# 1-POWER.net
KiCad netlist of a schematic drawn in Altium Designer
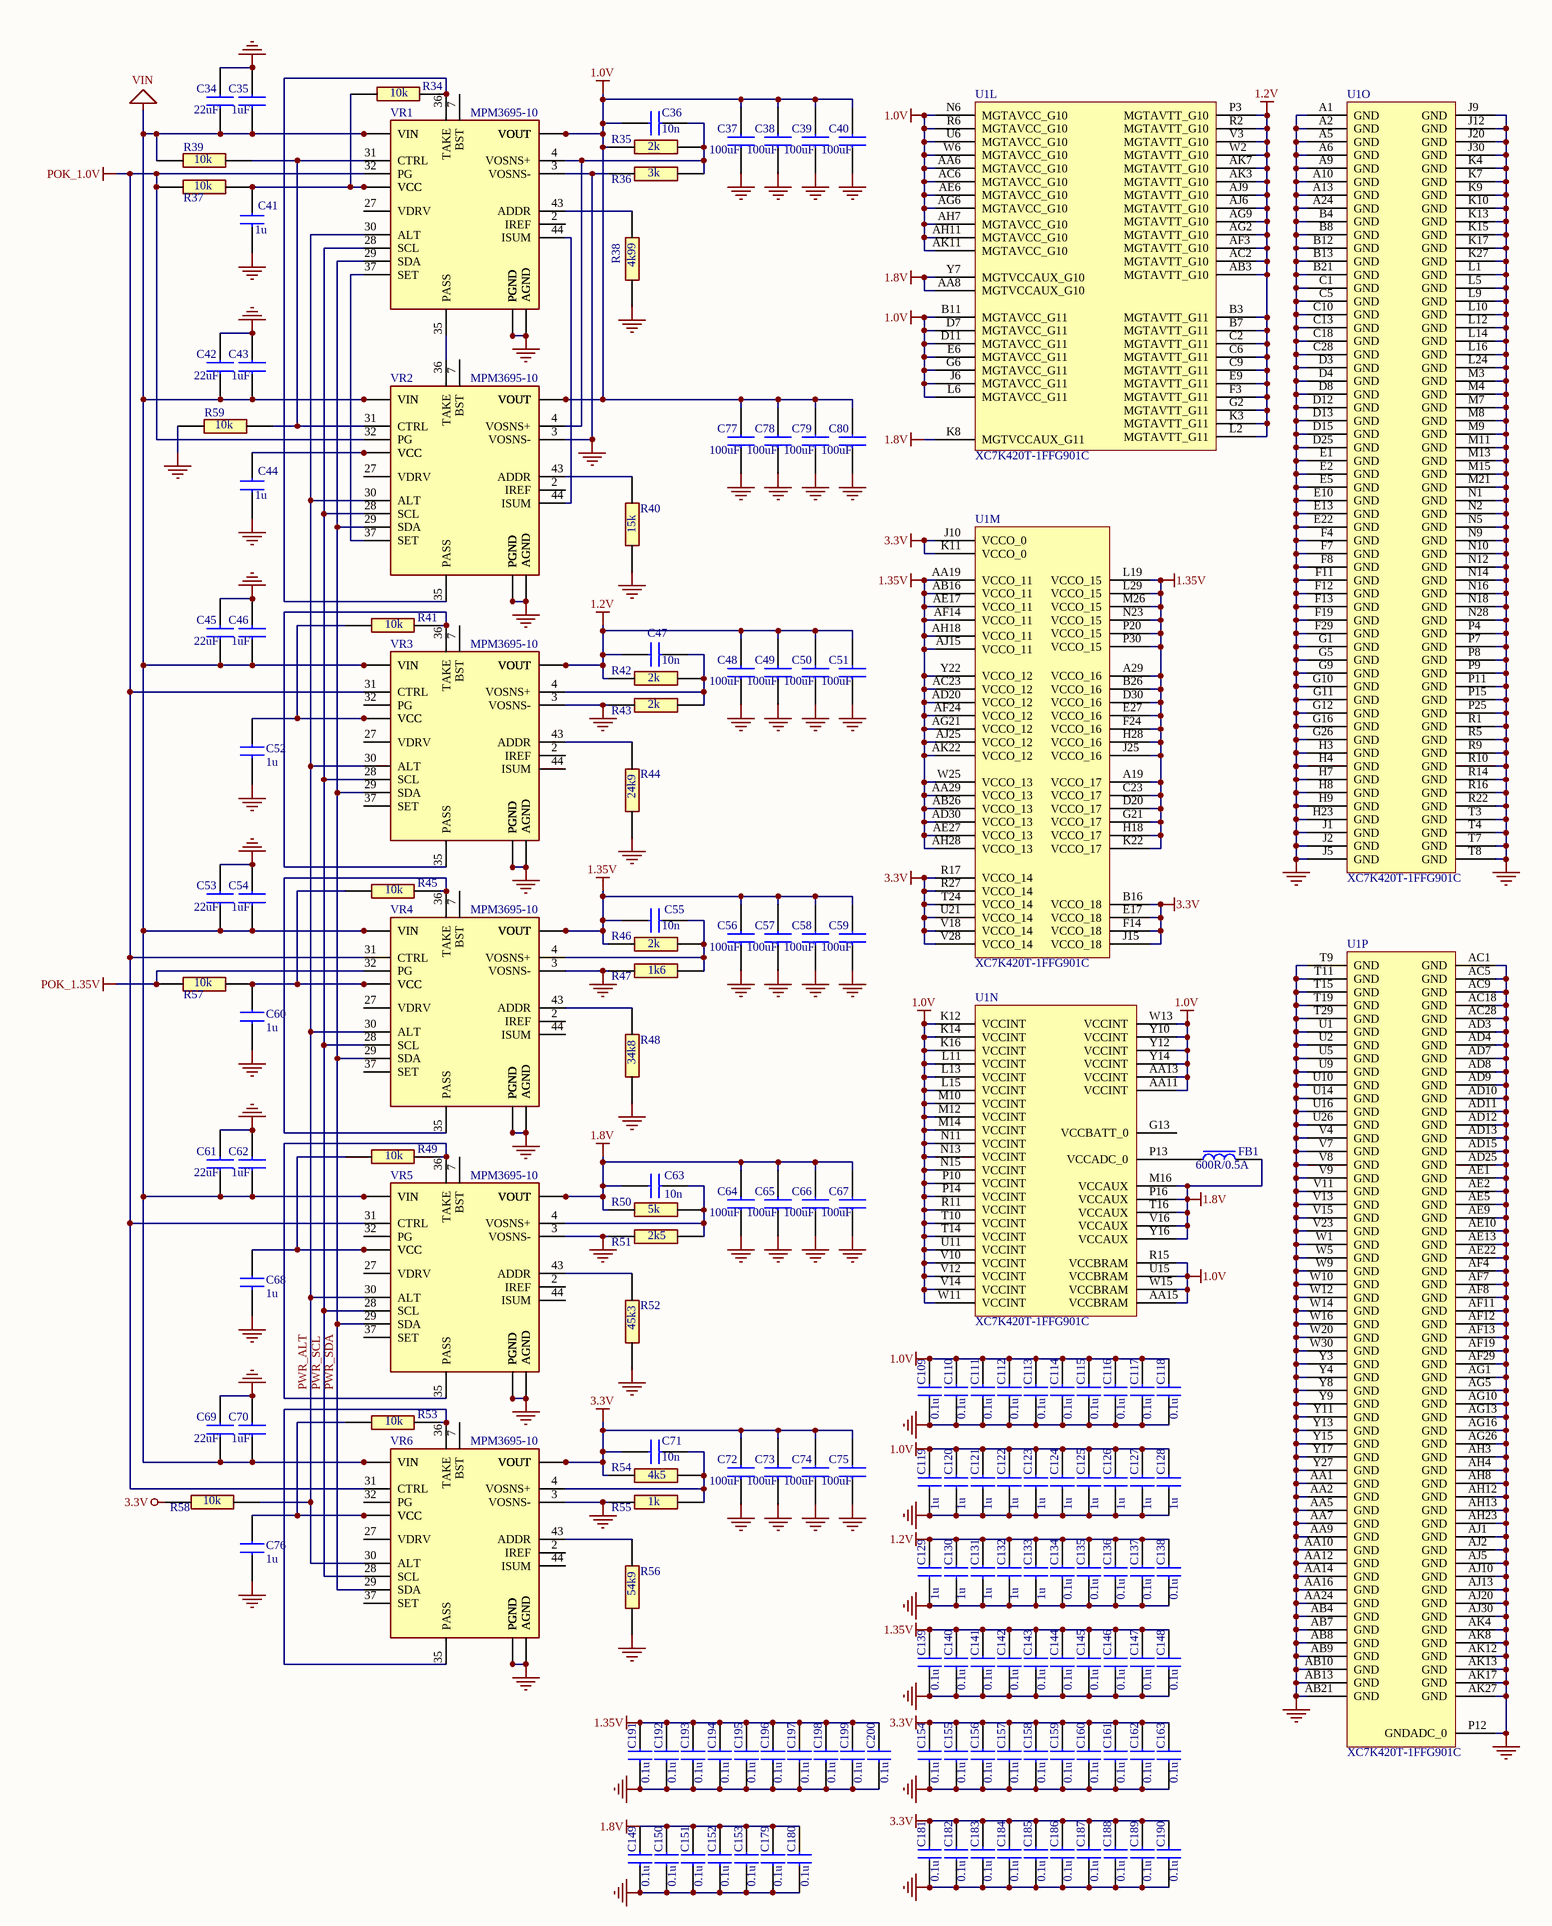
[diagram p0: 1-POWER.SchDoc]

(export (version "E")
  (design (tool "Eeschema 10.0.6"))
  (components
    (comp (ref "C34")
      (value "22uF")
      (footprint "CAPC3225X280N")
      (description "Capacitor")
      (fields
        (field (name "MANUFACTURER_PART_NUMBER") "JMK325ABJ107MM-P")
        (field (name "MOUSER PART NUMBER") "963-JMK325ABJ107MM-P")
      )
      (libsource (lib "m-BLANC") (part "CAP 3225"))
    )
    (comp (ref "C35")
      (value "1uF")
      (footprint "CAPC3225X280N")
      (description "Capacitor")
      (fields
        (field (name "MANUFACTURER_PART_NUMBER") "JMK325ABJ107MM-P")
        (field (name "MOUSER PART NUMBER") "963-JMK325ABJ107MM-P")
      )
      (libsource (lib "m-BLANC") (part "CAP 3225"))
    )
    (comp (ref "C36")
      (value "10n")
      (footprint "SMD0402")
      (description "Capacitor")
      (libsource (lib "m-BLANC") (part "CAP 0402"))
    )
    (comp (ref "C37")
      (value "100uF")
      (footprint "CAPC3225X280N")
      (description "Capacitor")
      (fields
        (field (name "MANUFACTURER_PART_NUMBER") "JMK325ABJ107MM-P")
        (field (name "MOUSER PART NUMBER") "963-JMK325ABJ107MM-P")
      )
      (libsource (lib "m-BLANC") (part "CAP 3225"))
    )
    (comp (ref "C38")
      (value "100uF")
      (footprint "CAPC3225X280N")
      (description "Capacitor")
      (fields
        (field (name "MANUFACTURER_PART_NUMBER") "JMK325ABJ107MM-P")
        (field (name "MOUSER PART NUMBER") "963-JMK325ABJ107MM-P")
      )
      (libsource (lib "m-BLANC") (part "CAP 3225"))
    )
    (comp (ref "C39")
      (value "100uF")
      (footprint "CAPC3225X280N")
      (description "Capacitor")
      (fields
        (field (name "MANUFACTURER_PART_NUMBER") "JMK325ABJ107MM-P")
        (field (name "MOUSER PART NUMBER") "963-JMK325ABJ107MM-P")
      )
      (libsource (lib "m-BLANC") (part "CAP 3225"))
    )
    (comp (ref "C40")
      (value "100uF")
      (footprint "CAPC3225X280N")
      (description "Capacitor")
      (fields
        (field (name "MANUFACTURER_PART_NUMBER") "JMK325ABJ107MM-P")
        (field (name "MOUSER PART NUMBER") "963-JMK325ABJ107MM-P")
      )
      (libsource (lib "m-BLANC") (part "CAP 3225"))
    )
    (comp (ref "C41")
      (value "1u")
      (footprint "SMD0402")
      (description "Capacitor")
      (libsource (lib "m-BLANC") (part "CAP 0402"))
    )
    (comp (ref "C42")
      (value "22uF")
      (footprint "CAPC3225X280N")
      (description "Capacitor")
      (fields
        (field (name "MANUFACTURER_PART_NUMBER") "JMK325ABJ107MM-P")
        (field (name "MOUSER PART NUMBER") "963-JMK325ABJ107MM-P")
      )
      (libsource (lib "m-BLANC") (part "CAP 3225"))
    )
    (comp (ref "C43")
      (value "1uF")
      (footprint "CAPC3225X280N")
      (description "Capacitor")
      (fields
        (field (name "MANUFACTURER_PART_NUMBER") "JMK325ABJ107MM-P")
        (field (name "MOUSER PART NUMBER") "963-JMK325ABJ107MM-P")
      )
      (libsource (lib "m-BLANC") (part "CAP 3225"))
    )
    (comp (ref "C44")
      (value "1u")
      (footprint "SMD0402")
      (description "Capacitor")
      (libsource (lib "m-BLANC") (part "CAP 0402"))
    )
    (comp (ref "C45")
      (value "22uF")
      (footprint "CAPC3225X280N")
      (description "Capacitor")
      (fields
        (field (name "MANUFACTURER_PART_NUMBER") "JMK325ABJ107MM-P")
        (field (name "MOUSER PART NUMBER") "963-JMK325ABJ107MM-P")
      )
      (libsource (lib "m-BLANC") (part "CAP 3225"))
    )
    (comp (ref "C46")
      (value "1uF")
      (footprint "CAPC3225X280N")
      (description "Capacitor")
      (fields
        (field (name "MANUFACTURER_PART_NUMBER") "JMK325ABJ107MM-P")
        (field (name "MOUSER PART NUMBER") "963-JMK325ABJ107MM-P")
      )
      (libsource (lib "m-BLANC") (part "CAP 3225"))
    )
    (comp (ref "C47")
      (value "10n")
      (footprint "SMD0402")
      (description "Capacitor")
      (libsource (lib "m-BLANC") (part "CAP 0402"))
    )
    (comp (ref "C48")
      (value "100uF")
      (footprint "CAPC3225X280N")
      (description "Capacitor")
      (fields
        (field (name "MANUFACTURER_PART_NUMBER") "JMK325ABJ107MM-P")
        (field (name "MOUSER PART NUMBER") "963-JMK325ABJ107MM-P")
      )
      (libsource (lib "m-BLANC") (part "CAP 3225"))
    )
    (comp (ref "C49")
      (value "100uF")
      (footprint "CAPC3225X280N")
      (description "Capacitor")
      (fields
        (field (name "MANUFACTURER_PART_NUMBER") "JMK325ABJ107MM-P")
        (field (name "MOUSER PART NUMBER") "963-JMK325ABJ107MM-P")
      )
      (libsource (lib "m-BLANC") (part "CAP 3225"))
    )
    (comp (ref "C50")
      (value "100uF")
      (footprint "CAPC3225X280N")
      (description "Capacitor")
      (fields
        (field (name "MANUFACTURER_PART_NUMBER") "JMK325ABJ107MM-P")
        (field (name "MOUSER PART NUMBER") "963-JMK325ABJ107MM-P")
      )
      (libsource (lib "m-BLANC") (part "CAP 3225"))
    )
    (comp (ref "C51")
      (value "100uF")
      (footprint "CAPC3225X280N")
      (description "Capacitor")
      (fields
        (field (name "MANUFACTURER_PART_NUMBER") "JMK325ABJ107MM-P")
        (field (name "MOUSER PART NUMBER") "963-JMK325ABJ107MM-P")
      )
      (libsource (lib "m-BLANC") (part "CAP 3225"))
    )
    (comp (ref "C52")
      (value "1u")
      (footprint "SMD0402")
      (description "Capacitor")
      (libsource (lib "m-BLANC") (part "CAP 0402"))
    )
    (comp (ref "C53")
      (value "22uF")
      (footprint "CAPC3225X280N")
      (description "Capacitor")
      (fields
        (field (name "MANUFACTURER_PART_NUMBER") "JMK325ABJ107MM-P")
        (field (name "MOUSER PART NUMBER") "963-JMK325ABJ107MM-P")
      )
      (libsource (lib "m-BLANC") (part "CAP 3225"))
    )
    (comp (ref "C54")
      (value "1uF")
      (footprint "CAPC3225X280N")
      (description "Capacitor")
      (fields
        (field (name "MANUFACTURER_PART_NUMBER") "JMK325ABJ107MM-P")
        (field (name "MOUSER PART NUMBER") "963-JMK325ABJ107MM-P")
      )
      (libsource (lib "m-BLANC") (part "CAP 3225"))
    )
    (comp (ref "C55")
      (value "10n")
      (footprint "SMD0402")
      (description "Capacitor")
      (libsource (lib "m-BLANC") (part "CAP 0402"))
    )
    (comp (ref "C56")
      (value "100uF")
      (footprint "CAPC3225X280N")
      (description "Capacitor")
      (fields
        (field (name "MANUFACTURER_PART_NUMBER") "JMK325ABJ107MM-P")
        (field (name "MOUSER PART NUMBER") "963-JMK325ABJ107MM-P")
      )
      (libsource (lib "m-BLANC") (part "CAP 3225"))
    )
    (comp (ref "C57")
      (value "100uF")
      (footprint "CAPC3225X280N")
      (description "Capacitor")
      (fields
        (field (name "MANUFACTURER_PART_NUMBER") "JMK325ABJ107MM-P")
        (field (name "MOUSER PART NUMBER") "963-JMK325ABJ107MM-P")
      )
      (libsource (lib "m-BLANC") (part "CAP 3225"))
    )
    (comp (ref "C58")
      (value "100uF")
      (footprint "CAPC3225X280N")
      (description "Capacitor")
      (fields
        (field (name "MANUFACTURER_PART_NUMBER") "JMK325ABJ107MM-P")
        (field (name "MOUSER PART NUMBER") "963-JMK325ABJ107MM-P")
      )
      (libsource (lib "m-BLANC") (part "CAP 3225"))
    )
    (comp (ref "C59")
      (value "100uF")
      (footprint "CAPC3225X280N")
      (description "Capacitor")
      (fields
        (field (name "MANUFACTURER_PART_NUMBER") "JMK325ABJ107MM-P")
        (field (name "MOUSER PART NUMBER") "963-JMK325ABJ107MM-P")
      )
      (libsource (lib "m-BLANC") (part "CAP 3225"))
    )
    (comp (ref "C60")
      (value "1u")
      (footprint "SMD0402")
      (description "Capacitor")
      (libsource (lib "m-BLANC") (part "CAP 0402"))
    )
    (comp (ref "C61")
      (value "22uF")
      (footprint "CAPC3225X280N")
      (description "Capacitor")
      (fields
        (field (name "MANUFACTURER_PART_NUMBER") "JMK325ABJ107MM-P")
        (field (name "MOUSER PART NUMBER") "963-JMK325ABJ107MM-P")
      )
      (libsource (lib "m-BLANC") (part "CAP 3225"))
    )
    (comp (ref "C62")
      (value "1uF")
      (footprint "CAPC3225X280N")
      (description "Capacitor")
      (fields
        (field (name "MANUFACTURER_PART_NUMBER") "JMK325ABJ107MM-P")
        (field (name "MOUSER PART NUMBER") "963-JMK325ABJ107MM-P")
      )
      (libsource (lib "m-BLANC") (part "CAP 3225"))
    )
    (comp (ref "C63")
      (value "10n")
      (footprint "SMD0402")
      (description "Capacitor")
      (libsource (lib "m-BLANC") (part "CAP 0402"))
    )
    (comp (ref "C64")
      (value "100uF")
      (footprint "CAPC3225X280N")
      (description "Capacitor")
      (fields
        (field (name "MANUFACTURER_PART_NUMBER") "JMK325ABJ107MM-P")
        (field (name "MOUSER PART NUMBER") "963-JMK325ABJ107MM-P")
      )
      (libsource (lib "m-BLANC") (part "CAP 3225"))
    )
    (comp (ref "C65")
      (value "100uF")
      (footprint "CAPC3225X280N")
      (description "Capacitor")
      (fields
        (field (name "MANUFACTURER_PART_NUMBER") "JMK325ABJ107MM-P")
        (field (name "MOUSER PART NUMBER") "963-JMK325ABJ107MM-P")
      )
      (libsource (lib "m-BLANC") (part "CAP 3225"))
    )
    (comp (ref "C66")
      (value "100uF")
      (footprint "CAPC3225X280N")
      (description "Capacitor")
      (fields
        (field (name "MANUFACTURER_PART_NUMBER") "JMK325ABJ107MM-P")
        (field (name "MOUSER PART NUMBER") "963-JMK325ABJ107MM-P")
      )
      (libsource (lib "m-BLANC") (part "CAP 3225"))
    )
    (comp (ref "C67")
      (value "100uF")
      (footprint "CAPC3225X280N")
      (description "Capacitor")
      (fields
        (field (name "MANUFACTURER_PART_NUMBER") "JMK325ABJ107MM-P")
        (field (name "MOUSER PART NUMBER") "963-JMK325ABJ107MM-P")
      )
      (libsource (lib "m-BLANC") (part "CAP 3225"))
    )
    (comp (ref "C68")
      (value "1u")
      (footprint "SMD0402")
      (description "Capacitor")
      (libsource (lib "m-BLANC") (part "CAP 0402"))
    )
    (comp (ref "C69")
      (value "22uF")
      (footprint "CAPC3225X280N")
      (description "Capacitor")
      (fields
        (field (name "MANUFACTURER_PART_NUMBER") "JMK325ABJ107MM-P")
        (field (name "MOUSER PART NUMBER") "963-JMK325ABJ107MM-P")
      )
      (libsource (lib "") (part "CAP 3225_1"))
    )
    (comp (ref "C70")
      (value "1uF")
      (footprint "CAPC3225X280N")
      (description "Capacitor")
      (fields
        (field (name "MANUFACTURER_PART_NUMBER") "JMK325ABJ107MM-P")
        (field (name "MOUSER PART NUMBER") "963-JMK325ABJ107MM-P")
      )
      (libsource (lib "") (part "CAP 3225_1"))
    )
    (comp (ref "C71")
      (value "10n")
      (footprint "SMD0402")
      (description "Capacitor")
      (libsource (lib "m-BLANC") (part "CAP 0402"))
    )
    (comp (ref "C72")
      (value "100uF")
      (footprint "CAPC3225X280N")
      (description "Capacitor")
      (fields
        (field (name "MANUFACTURER_PART_NUMBER") "JMK325ABJ107MM-P")
        (field (name "MOUSER PART NUMBER") "963-JMK325ABJ107MM-P")
      )
      (libsource (lib "m-BLANC") (part "CAP 3225"))
    )
    (comp (ref "C73")
      (value "100uF")
      (footprint "CAPC3225X280N")
      (description "Capacitor")
      (fields
        (field (name "MANUFACTURER_PART_NUMBER") "JMK325ABJ107MM-P")
        (field (name "MOUSER PART NUMBER") "963-JMK325ABJ107MM-P")
      )
      (libsource (lib "m-BLANC") (part "CAP 3225"))
    )
    (comp (ref "C74")
      (value "100uF")
      (footprint "CAPC3225X280N")
      (description "Capacitor")
      (fields
        (field (name "MANUFACTURER_PART_NUMBER") "JMK325ABJ107MM-P")
        (field (name "MOUSER PART NUMBER") "963-JMK325ABJ107MM-P")
      )
      (libsource (lib "m-BLANC") (part "CAP 3225"))
    )
    (comp (ref "C75")
      (value "100uF")
      (footprint "CAPC3225X280N")
      (description "Capacitor")
      (fields
        (field (name "MANUFACTURER_PART_NUMBER") "JMK325ABJ107MM-P")
        (field (name "MOUSER PART NUMBER") "963-JMK325ABJ107MM-P")
      )
      (libsource (lib "m-BLANC") (part "CAP 3225"))
    )
    (comp (ref "C76")
      (value "1u")
      (footprint "SMD0402")
      (description "Capacitor")
      (libsource (lib "m-BLANC") (part "CAP 0402"))
    )
    (comp (ref "C77")
      (value "100uF")
      (footprint "CAPC3225X280N")
      (description "Capacitor")
      (fields
        (field (name "MANUFACTURER_PART_NUMBER") "JMK325ABJ107MM-P")
        (field (name "MOUSER PART NUMBER") "963-JMK325ABJ107MM-P")
      )
      (libsource (lib "m-BLANC") (part "CAP 3225"))
    )
    (comp (ref "C78")
      (value "100uF")
      (footprint "CAPC3225X280N")
      (description "Capacitor")
      (fields
        (field (name "MANUFACTURER_PART_NUMBER") "JMK325ABJ107MM-P")
        (field (name "MOUSER PART NUMBER") "963-JMK325ABJ107MM-P")
      )
      (libsource (lib "m-BLANC") (part "CAP 3225"))
    )
    (comp (ref "C79")
      (value "100uF")
      (footprint "CAPC3225X280N")
      (description "Capacitor")
      (fields
        (field (name "MANUFACTURER_PART_NUMBER") "JMK325ABJ107MM-P")
        (field (name "MOUSER PART NUMBER") "963-JMK325ABJ107MM-P")
      )
      (libsource (lib "m-BLANC") (part "CAP 3225"))
    )
    (comp (ref "C80")
      (value "100uF")
      (footprint "CAPC3225X280N")
      (description "Capacitor")
      (fields
        (field (name "MANUFACTURER_PART_NUMBER") "JMK325ABJ107MM-P")
        (field (name "MOUSER PART NUMBER") "963-JMK325ABJ107MM-P")
      )
      (libsource (lib "m-BLANC") (part "CAP 3225"))
    )
    (comp (ref "C109")
      (value "0.1u")
      (footprint "SMD0402")
      (description "Capacitor")
      (libsource (lib "") (part "CAP 0402_1"))
    )
    (comp (ref "C110")
      (value "0.1u")
      (footprint "SMD0402")
      (description "Capacitor")
      (libsource (lib "") (part "CAP 0402_1"))
    )
    (comp (ref "C111")
      (value "0.1u")
      (footprint "SMD0402")
      (description "Capacitor")
      (libsource (lib "") (part "CAP 0402_1"))
    )
    (comp (ref "C112")
      (value "0.1u")
      (footprint "SMD0402")
      (description "Capacitor")
      (libsource (lib "") (part "CAP 0402_1"))
    )
    (comp (ref "C113")
      (value "0.1u")
      (footprint "SMD0402")
      (description "Capacitor")
      (libsource (lib "") (part "CAP 0402_1"))
    )
    (comp (ref "C114")
      (value "0.1u")
      (footprint "SMD0402")
      (description "Capacitor")
      (libsource (lib "") (part "CAP 0402_1"))
    )
    (comp (ref "C115")
      (value "0.1u")
      (footprint "SMD0402")
      (description "Capacitor")
      (libsource (lib "") (part "CAP 0402_1"))
    )
    (comp (ref "C116")
      (value "0.1u")
      (footprint "SMD0402")
      (description "Capacitor")
      (libsource (lib "") (part "CAP 0402_1"))
    )
    (comp (ref "C117")
      (value "0.1u")
      (footprint "SMD0402")
      (description "Capacitor")
      (libsource (lib "") (part "CAP 0402_1"))
    )
    (comp (ref "C118")
      (value "0.1u")
      (footprint "SMD0402")
      (description "Capacitor")
      (libsource (lib "") (part "CAP 0402_1"))
    )
    (comp (ref "C119")
      (value "1u")
      (footprint "SMD0402")
      (description "Capacitor")
      (libsource (lib "m-BLANC") (part "CAP 0402"))
    )
    (comp (ref "C120")
      (value "1u")
      (footprint "SMD0402")
      (description "Capacitor")
      (libsource (lib "m-BLANC") (part "CAP 0402"))
    )
    (comp (ref "C121")
      (value "1u")
      (footprint "SMD0402")
      (description "Capacitor")
      (libsource (lib "m-BLANC") (part "CAP 0402"))
    )
    (comp (ref "C122")
      (value "1u")
      (footprint "SMD0402")
      (description "Capacitor")
      (libsource (lib "m-BLANC") (part "CAP 0402"))
    )
    (comp (ref "C123")
      (value "1u")
      (footprint "SMD0402")
      (description "Capacitor")
      (libsource (lib "m-BLANC") (part "CAP 0402"))
    )
    (comp (ref "C124")
      (value "1u")
      (footprint "SMD0402")
      (description "Capacitor")
      (libsource (lib "m-BLANC") (part "CAP 0402"))
    )
    (comp (ref "C125")
      (value "1u")
      (footprint "SMD0402")
      (description "Capacitor")
      (libsource (lib "m-BLANC") (part "CAP 0402"))
    )
    (comp (ref "C126")
      (value "1u")
      (footprint "SMD0402")
      (description "Capacitor")
      (libsource (lib "m-BLANC") (part "CAP 0402"))
    )
    (comp (ref "C127")
      (value "1u")
      (footprint "SMD0402")
      (description "Capacitor")
      (libsource (lib "m-BLANC") (part "CAP 0402"))
    )
    (comp (ref "C128")
      (value "1u")
      (footprint "SMD0402")
      (description "Capacitor")
      (libsource (lib "m-BLANC") (part "CAP 0402"))
    )
    (comp (ref "C129")
      (value "1u")
      (footprint "SMD0402")
      (description "Capacitor")
      (libsource (lib "m-BLANC") (part "CAP 0402"))
    )
    (comp (ref "C130")
      (value "1u")
      (footprint "SMD0402")
      (description "Capacitor")
      (libsource (lib "m-BLANC") (part "CAP 0402"))
    )
    (comp (ref "C131")
      (value "1u")
      (footprint "SMD0402")
      (description "Capacitor")
      (libsource (lib "m-BLANC") (part "CAP 0402"))
    )
    (comp (ref "C132")
      (value "1u")
      (footprint "SMD0402")
      (description "Capacitor")
      (libsource (lib "m-BLANC") (part "CAP 0402"))
    )
    (comp (ref "C133")
      (value "1u")
      (footprint "SMD0402")
      (description "Capacitor")
      (libsource (lib "m-BLANC") (part "CAP 0402"))
    )
    (comp (ref "C134")
      (value "0.1u")
      (footprint "SMD0402")
      (description "Capacitor")
      (libsource (lib "m-BLANC") (part "CAP 0402"))
    )
    (comp (ref "C135")
      (value "0.1u")
      (footprint "SMD0402")
      (description "Capacitor")
      (libsource (lib "m-BLANC") (part "CAP 0402"))
    )
    (comp (ref "C136")
      (value "0.1u")
      (footprint "SMD0402")
      (description "Capacitor")
      (libsource (lib "m-BLANC") (part "CAP 0402"))
    )
    (comp (ref "C137")
      (value "0.1u")
      (footprint "SMD0402")
      (description "Capacitor")
      (libsource (lib "m-BLANC") (part "CAP 0402"))
    )
    (comp (ref "C138")
      (value "0.1u")
      (footprint "SMD0402")
      (description "Capacitor")
      (libsource (lib "m-BLANC") (part "CAP 0402"))
    )
    (comp (ref "C139")
      (value "0.1u")
      (footprint "SMD0402")
      (description "Capacitor")
      (libsource (lib "m-BLANC") (part "CAP 0402"))
    )
    (comp (ref "C140")
      (value "0.1u")
      (footprint "SMD0402")
      (description "Capacitor")
      (libsource (lib "m-BLANC") (part "CAP 0402"))
    )
    (comp (ref "C141")
      (value "0.1u")
      (footprint "SMD0402")
      (description "Capacitor")
      (libsource (lib "m-BLANC") (part "CAP 0402"))
    )
    (comp (ref "C142")
      (value "0.1u")
      (footprint "SMD0402")
      (description "Capacitor")
      (libsource (lib "m-BLANC") (part "CAP 0402"))
    )
    (comp (ref "C143")
      (value "0.1u")
      (footprint "SMD0402")
      (description "Capacitor")
      (libsource (lib "m-BLANC") (part "CAP 0402"))
    )
    (comp (ref "C144")
      (value "0.1u")
      (footprint "SMD0402")
      (description "Capacitor")
      (libsource (lib "m-BLANC") (part "CAP 0402"))
    )
    (comp (ref "C145")
      (value "0.1u")
      (footprint "SMD0402")
      (description "Capacitor")
      (libsource (lib "m-BLANC") (part "CAP 0402"))
    )
    (comp (ref "C146")
      (value "0.1u")
      (footprint "SMD0402")
      (description "Capacitor")
      (libsource (lib "m-BLANC") (part "CAP 0402"))
    )
    (comp (ref "C147")
      (value "0.1u")
      (footprint "SMD0402")
      (description "Capacitor")
      (libsource (lib "m-BLANC") (part "CAP 0402"))
    )
    (comp (ref "C148")
      (value "0.1u")
      (footprint "SMD0402")
      (description "Capacitor")
      (libsource (lib "m-BLANC") (part "CAP 0402"))
    )
    (comp (ref "C149")
      (value "0.1u")
      (footprint "SMD0402")
      (description "Capacitor")
      (libsource (lib "m-BLANC") (part "CAP 0402"))
    )
    (comp (ref "C150")
      (value "0.1u")
      (footprint "SMD0402")
      (description "Capacitor")
      (libsource (lib "m-BLANC") (part "CAP 0402"))
    )
    (comp (ref "C151")
      (value "0.1u")
      (footprint "SMD0402")
      (description "Capacitor")
      (libsource (lib "m-BLANC") (part "CAP 0402"))
    )
    (comp (ref "C152")
      (value "0.1u")
      (footprint "SMD0402")
      (description "Capacitor")
      (libsource (lib "m-BLANC") (part "CAP 0402"))
    )
    (comp (ref "C153")
      (value "0.1u")
      (footprint "SMD0402")
      (description "Capacitor")
      (libsource (lib "m-BLANC") (part "CAP 0402"))
    )
    (comp (ref "C154")
      (value "0.1u")
      (footprint "SMD0402")
      (description "Capacitor")
      (libsource (lib "m-BLANC") (part "CAP 0402"))
    )
    (comp (ref "C155")
      (value "0.1u")
      (footprint "SMD0402")
      (description "Capacitor")
      (libsource (lib "m-BLANC") (part "CAP 0201"))
    )
    (comp (ref "C156")
      (value "0.1u")
      (footprint "SMD0402")
      (description "Capacitor")
      (libsource (lib "m-BLANC") (part "CAP 0402"))
    )
    (comp (ref "C157")
      (value "0.1u")
      (footprint "SMD0402")
      (description "Capacitor")
      (libsource (lib "m-BLANC") (part "CAP 0402"))
    )
    (comp (ref "C158")
      (value "0.1u")
      (footprint "SMD0402")
      (description "Capacitor")
      (libsource (lib "m-BLANC") (part "CAP 0402"))
    )
    (comp (ref "C159")
      (value "0.1u")
      (footprint "SMD0402")
      (description "Capacitor")
      (libsource (lib "m-BLANC") (part "CAP 0402"))
    )
    (comp (ref "C160")
      (value "0.1u")
      (footprint "SMD0402")
      (description "Capacitor")
      (libsource (lib "m-BLANC") (part "CAP 0402"))
    )
    (comp (ref "C161")
      (value "0.1u")
      (footprint "SMD0402")
      (description "Capacitor")
      (libsource (lib "m-BLANC") (part "CAP 0402"))
    )
    (comp (ref "C162")
      (value "0.1u")
      (footprint "SMD0402")
      (description "Capacitor")
      (libsource (lib "m-BLANC") (part "CAP 0402"))
    )
    (comp (ref "C163")
      (value "0.1u")
      (footprint "SMD0402")
      (description "Capacitor")
      (libsource (lib "m-BLANC") (part "CAP 0402"))
    )
    (comp (ref "C179")
      (value "0.1u")
      (footprint "SMD0402")
      (description "Capacitor")
      (libsource (lib "m-BLANC") (part "CAP 0402"))
    )
    (comp (ref "C180")
      (value "0.1u")
      (footprint "SMD0402")
      (description "Capacitor")
      (libsource (lib "m-BLANC") (part "CAP 0402"))
    )
    (comp (ref "C181")
      (value "0.1u")
      (footprint "SMD0402")
      (description "Capacitor")
      (libsource (lib "m-BLANC") (part "CAP 0402"))
    )
    (comp (ref "C182")
      (value "0.1u")
      (footprint "SMD0402")
      (description "Capacitor")
      (libsource (lib "m-BLANC") (part "CAP 0201"))
    )
    (comp (ref "C183")
      (value "0.1u")
      (footprint "SMD0402")
      (description "Capacitor")
      (libsource (lib "m-BLANC") (part "CAP 0402"))
    )
    (comp (ref "C184")
      (value "0.1u")
      (footprint "SMD0402")
      (description "Capacitor")
      (libsource (lib "m-BLANC") (part "CAP 0402"))
    )
    (comp (ref "C185")
      (value "0.1u")
      (footprint "SMD0402")
      (description "Capacitor")
      (libsource (lib "m-BLANC") (part "CAP 0402"))
    )
    (comp (ref "C186")
      (value "0.1u")
      (footprint "SMD0402")
      (description "Capacitor")
      (libsource (lib "m-BLANC") (part "CAP 0402"))
    )
    (comp (ref "C187")
      (value "0.1u")
      (footprint "SMD0402")
      (description "Capacitor")
      (libsource (lib "m-BLANC") (part "CAP 0402"))
    )
    (comp (ref "C188")
      (value "0.1u")
      (footprint "SMD0402")
      (description "Capacitor")
      (libsource (lib "m-BLANC") (part "CAP 0402"))
    )
    (comp (ref "C189")
      (value "0.1u")
      (footprint "SMD0402")
      (description "Capacitor")
      (libsource (lib "m-BLANC") (part "CAP 0402"))
    )
    (comp (ref "C190")
      (value "0.1u")
      (footprint "SMD0402")
      (description "Capacitor")
      (libsource (lib "m-BLANC") (part "CAP 0402"))
    )
    (comp (ref "C191")
      (value "0.1u")
      (footprint "SMD0402")
      (description "Capacitor")
      (libsource (lib "m-BLANC") (part "CAP 0402"))
    )
    (comp (ref "C192")
      (value "0.1u")
      (footprint "SMD0402")
      (description "Capacitor")
      (libsource (lib "m-BLANC") (part "CAP 0402"))
    )
    (comp (ref "C193")
      (value "0.1u")
      (footprint "SMD0402")
      (description "Capacitor")
      (libsource (lib "m-BLANC") (part "CAP 0402"))
    )
    (comp (ref "C194")
      (value "0.1u")
      (footprint "SMD0402")
      (description "Capacitor")
      (libsource (lib "m-BLANC") (part "CAP 0402"))
    )
    (comp (ref "C195")
      (value "0.1u")
      (footprint "SMD0402")
      (description "Capacitor")
      (libsource (lib "m-BLANC") (part "CAP 0402"))
    )
    (comp (ref "C196")
      (value "0.1u")
      (footprint "SMD0402")
      (description "Capacitor")
      (libsource (lib "m-BLANC") (part "CAP 0402"))
    )
    (comp (ref "C197")
      (value "0.1u")
      (footprint "SMD0402")
      (description "Capacitor")
      (libsource (lib "m-BLANC") (part "CAP 0402"))
    )
    (comp (ref "C198")
      (value "0.1u")
      (footprint "SMD0402")
      (description "Capacitor")
      (libsource (lib "m-BLANC") (part "CAP 0402"))
    )
    (comp (ref "C199")
      (value "0.1u")
      (footprint "SMD0402")
      (description "Capacitor")
      (libsource (lib "m-BLANC") (part "CAP 0402"))
    )
    (comp (ref "C200")
      (value "0.1u")
      (footprint "SMD0402")
      (description "Capacitor")
      (libsource (lib "m-BLANC") (part "CAP 0402"))
    )
    (comp (ref "FB1")
      (value "600R/0.5A")
      (footprint "SMD0402")
      (description "Ferrite Bead")
      (libsource (lib "m-BLANC") (part "FERRITE 0402"))
    )
    (comp (ref "R34")
      (value "10k")
      (footprint "SMD0402")
      (description "Resistor")
      (libsource (lib "m-BLANC") (part "RES 0201"))
    )
    (comp (ref "R35")
      (value "2k")
      (footprint "SMD0402")
      (description "Resistor")
      (libsource (lib "") (part "RES 0402_1"))
    )
    (comp (ref "R36")
      (value "3k")
      (footprint "SMD0402")
      (description "Resistor")
      (libsource (lib "") (part "RES 0402_1"))
    )
    (comp (ref "R37")
      (value "10k")
      (footprint "SMD0402")
      (description "Resistor")
      (libsource (lib "") (part "RES 0402_1"))
    )
    (comp (ref "R38")
      (value "4k99")
      (footprint "SMD0402")
      (description "Resistor")
      (libsource (lib "m-BLANC") (part "RES 0402"))
    )
    (comp (ref "R39")
      (value "10k")
      (footprint "SMD0402")
      (description "Resistor")
      (libsource (lib "") (part "RES 0402_1"))
    )
    (comp (ref "R40")
      (value "15k")
      (footprint "SMD0402")
      (description "Resistor")
      (libsource (lib "m-BLANC") (part "RES 0402"))
    )
    (comp (ref "R41")
      (value "10k")
      (footprint "SMD0402")
      (description "Resistor")
      (libsource (lib "") (part "RES 0402_2"))
    )
    (comp (ref "R42")
      (value "2k")
      (footprint "SMD0402")
      (description "Resistor")
      (libsource (lib "") (part "RES 0402_1"))
    )
    (comp (ref "R43")
      (value "2k")
      (footprint "SMD0402")
      (description "Resistor")
      (libsource (lib "") (part "RES 0402_1"))
    )
    (comp (ref "R44")
      (value "24k9")
      (footprint "SMD0402")
      (description "Resistor")
      (libsource (lib "m-BLANC") (part "RES 0402"))
    )
    (comp (ref "R45")
      (value "10k")
      (footprint "SMD0402")
      (description "Resistor")
      (libsource (lib "") (part "RES 0402_2"))
    )
    (comp (ref "R46")
      (value "2k")
      (footprint "SMD0402")
      (description "Resistor")
      (libsource (lib "") (part "RES 0402_1"))
    )
    (comp (ref "R47")
      (value "1k6")
      (footprint "SMD0402")
      (description "Resistor")
      (libsource (lib "") (part "RES 0402_1"))
    )
    (comp (ref "R48")
      (value "34k8")
      (footprint "SMD0402")
      (description "Resistor")
      (libsource (lib "m-BLANC") (part "RES 0402"))
    )
    (comp (ref "R49")
      (value "10k")
      (footprint "SMD0402")
      (description "Resistor")
      (libsource (lib "") (part "RES 0402_2"))
    )
    (comp (ref "R50")
      (value "5k")
      (footprint "SMD0402")
      (description "Resistor")
      (libsource (lib "") (part "RES 0402_1"))
    )
    (comp (ref "R51")
      (value "2k5")
      (footprint "SMD0402")
      (description "Resistor")
      (libsource (lib "") (part "RES 0402_1"))
    )
    (comp (ref "R52")
      (value "45k3")
      (footprint "SMD0402")
      (description "Resistor")
      (libsource (lib "m-BLANC") (part "RES 0402"))
    )
    (comp (ref "R53")
      (value "10k")
      (footprint "SMD0402")
      (description "Resistor")
      (libsource (lib "") (part "RES 0402_2"))
    )
    (comp (ref "R54")
      (value "4k5")
      (footprint "SMD0402")
      (description "Resistor")
      (libsource (lib "") (part "RES 0402_1"))
    )
    (comp (ref "R55")
      (value "1k")
      (footprint "SMD0402")
      (description "Resistor")
      (libsource (lib "") (part "RES 0402_1"))
    )
    (comp (ref "R56")
      (value "54k9")
      (footprint "SMD0402")
      (description "Resistor")
      (libsource (lib "m-BLANC") (part "RES 0402"))
    )
    (comp (ref "R57")
      (value "10k")
      (footprint "SMD0402")
      (description "Resistor")
      (libsource (lib "") (part "RES 0402_1"))
    )
    (comp (ref "R58")
      (value "10k")
      (footprint "SMD0402")
      (description "Resistor")
      (libsource (lib "") (part "RES 0402_2"))
    )
    (comp (ref "R59")
      (value "10k")
      (footprint "SMD0402")
      (description "Resistor")
      (libsource (lib "") (part "RES 0402_1"))
    )
    (comp (ref "U1")
      (value "XC7K420T-1FFG901C")
      (footprint "FFG901")
      (description "Kintex-7 FPGA, 400 User I/Os, 28 GTX, 900-Ball BGA, Speed Grade 1, Commercial Grade, Pb-Free")
      (fields (field (name "GENERIC PART NUMBER") "XC7K420T") (field (name "MANUFACTURER") "Xilinx"))
      (libsource (lib "") (part "XC7K420T-1FFG901C_2"))
    )
    (comp (ref "VR1")
      (value "MPM3695-10")
      (footprint "QFN45-MPM3695-10")
      (description "16V, 10A, Scalable, Ultra-Thin DC/DC Power Module with PMBus")
      (libsource (lib "") (part "MPM3695-10_1"))
    )
    (comp (ref "VR2")
      (value "MPM3695-10")
      (footprint "QFN45-MPM3695-10")
      (description "16V, 10A, Scalable, Ultra-Thin DC/DC Power Module with PMBus")
      (libsource (lib "") (part "MPM3695-10_1"))
    )
    (comp (ref "VR3")
      (value "MPM3695-10")
      (footprint "QFN45-MPM3695-10")
      (description "16V, 10A, Scalable, Ultra-Thin DC/DC Power Module with PMBus")
      (libsource (lib "") (part "MPM3695-10_1"))
    )
    (comp (ref "VR4")
      (value "MPM3695-10")
      (footprint "QFN45-MPM3695-10")
      (description "16V, 10A, Scalable, Ultra-Thin DC/DC Power Module with PMBus")
      (libsource (lib "") (part "MPM3695-10_1"))
    )
    (comp (ref "VR5")
      (value "MPM3695-10")
      (footprint "QFN45-MPM3695-10")
      (description "16V, 10A, Scalable, Ultra-Thin DC/DC Power Module with PMBus")
      (libsource (lib "") (part "MPM3695-10_1"))
    )
    (comp (ref "VR6")
      (value "MPM3695-10")
      (footprint "QFN45-MPM3695-10")
      (description "16V, 10A, Scalable, Ultra-Thin DC/DC Power Module with PMBus")
      (libsource (lib "m-BLANC") (part "MPM3695-10"))
    )
  )
  (nets
    (net (code "1") (name "/PWR_ALT") (class "Default")
      (node (ref "R58") (pin "2") (pinfunction "2_2") (pintype "passive"))
      (node (ref "VR1") (pin "30") (pinfunction "ALT_30") (pintype "passive"))
      (node (ref "VR2") (pin "30") (pinfunction "ALT_30") (pintype "passive"))
      (node (ref "VR3") (pin "30") (pinfunction "ALT_30") (pintype "passive"))
      (node (ref "VR4") (pin "30") (pinfunction "ALT_30") (pintype "passive"))
      (node (ref "VR5") (pin "30") (pinfunction "ALT_30") (pintype "passive"))
      (node (ref "VR6") (pin "30") (pinfunction "ALT_30") (pintype "passive"))
    )
    (net (code "2") (name "/PWR_SCL") (class "Default")
      (node (ref "VR1") (pin "28") (pinfunction "SCL_28") (pintype "passive"))
      (node (ref "VR2") (pin "28") (pinfunction "SCL_28") (pintype "passive"))
      (node (ref "VR3") (pin "28") (pinfunction "SCL_28") (pintype "passive"))
      (node (ref "VR4") (pin "28") (pinfunction "SCL_28") (pintype "passive"))
      (node (ref "VR5") (pin "28") (pinfunction "SCL_28") (pintype "passive"))
      (node (ref "VR6") (pin "28") (pinfunction "SCL_28") (pintype "passive"))
    )
    (net (code "3") (name "/PWR_SDA") (class "Default")
      (node (ref "VR1") (pin "29") (pinfunction "SDA_29") (pintype "passive"))
      (node (ref "VR2") (pin "29") (pinfunction "SDA_29") (pintype "passive"))
      (node (ref "VR3") (pin "29") (pinfunction "SDA_29") (pintype "passive"))
      (node (ref "VR4") (pin "29") (pinfunction "SDA_29") (pintype "passive"))
      (node (ref "VR5") (pin "29") (pinfunction "SDA_29") (pintype "passive"))
      (node (ref "VR6") (pin "29") (pinfunction "SDA_29") (pintype "passive"))
    )
    (net (code "4") (name "1.0V") (class "Default")
      (node (ref "C109") (pin "2") (pinfunction "2_2") (pintype "passive"))
      (node (ref "C110") (pin "2") (pinfunction "2_2") (pintype "passive"))
      (node (ref "C111") (pin "2") (pinfunction "2_2") (pintype "passive"))
      (node (ref "C112") (pin "2") (pinfunction "2_2") (pintype "passive"))
      (node (ref "C113") (pin "2") (pinfunction "2_2") (pintype "passive"))
      (node (ref "C114") (pin "2") (pinfunction "2_2") (pintype "passive"))
      (node (ref "C115") (pin "2") (pinfunction "2_2") (pintype "passive"))
      (node (ref "C116") (pin "2") (pinfunction "2_2") (pintype "passive"))
      (node (ref "C117") (pin "2") (pinfunction "2_2") (pintype "passive"))
      (node (ref "C118") (pin "2") (pinfunction "2_2") (pintype "passive"))
      (node (ref "C119") (pin "2") (pinfunction "2_2") (pintype "passive"))
      (node (ref "C120") (pin "2") (pinfunction "2_2") (pintype "passive"))
      (node (ref "C121") (pin "2") (pinfunction "2_2") (pintype "passive"))
      (node (ref "C122") (pin "2") (pinfunction "2_2") (pintype "passive"))
      (node (ref "C123") (pin "2") (pinfunction "2_2") (pintype "passive"))
      (node (ref "C124") (pin "2") (pinfunction "2_2") (pintype "passive"))
      (node (ref "C125") (pin "2") (pinfunction "2_2") (pintype "passive"))
      (node (ref "C126") (pin "2") (pinfunction "2_2") (pintype "passive"))
      (node (ref "C127") (pin "2") (pinfunction "2_2") (pintype "passive"))
      (node (ref "C128") (pin "2") (pinfunction "2_2") (pintype "passive"))
      (node (ref "C36") (pin "1") (pinfunction "1_1") (pintype "passive"))
      (node (ref "C37") (pin "1") (pinfunction "1_1") (pintype "passive"))
      (node (ref "C38") (pin "1") (pinfunction "1_1") (pintype "passive"))
      (node (ref "C39") (pin "1") (pinfunction "1_1") (pintype "passive"))
      (node (ref "C40") (pin "1") (pinfunction "1_1") (pintype "passive"))
      (node (ref "C77") (pin "1") (pinfunction "1_1") (pintype "passive"))
      (node (ref "C78") (pin "1") (pinfunction "1_1") (pintype "passive"))
      (node (ref "C79") (pin "1") (pinfunction "1_1") (pintype "passive"))
      (node (ref "C80") (pin "1") (pinfunction "1_1") (pintype "passive"))
      (node (ref "R35") (pin "2") (pinfunction "2_2") (pintype "passive"))
      (node (ref "U1") (pin "AA11") (pinfunction "VCCINT_AA11") (pintype "power_in"))
      (node (ref "U1") (pin "AA13") (pinfunction "VCCINT_AA13") (pintype "power_in"))
      (node (ref "U1") (pin "AA15") (pinfunction "VCCBRAM_AA15") (pintype "power_in"))
      (node (ref "U1") (pin "AA6") (pinfunction "MGTAVCC_G10_AA6") (pintype "power_in"))
      (node (ref "U1") (pin "AC6") (pinfunction "MGTAVCC_G10_AC6") (pintype "power_in"))
      (node (ref "U1") (pin "AE6") (pinfunction "MGTAVCC_G10_AE6") (pintype "power_in"))
      (node (ref "U1") (pin "AG6") (pinfunction "MGTAVCC_G10_AG6") (pintype "power_in"))
      (node (ref "U1") (pin "AH11") (pinfunction "MGTAVCC_G10_AH11") (pintype "power_in"))
      (node (ref "U1") (pin "AH7") (pinfunction "MGTAVCC_G10_AH7") (pintype "power_in"))
      (node (ref "U1") (pin "AK11") (pinfunction "MGTAVCC_G10_AK11") (pintype "power_in"))
      (node (ref "U1") (pin "B11") (pinfunction "MGTAVCC_G11_B11") (pintype "power_in"))
      (node (ref "U1") (pin "D11") (pinfunction "MGTAVCC_G11_D11") (pintype "power_in"))
      (node (ref "U1") (pin "D7") (pinfunction "MGTAVCC_G11_D7") (pintype "power_in"))
      (node (ref "U1") (pin "E6") (pinfunction "MGTAVCC_G11_E6") (pintype "power_in"))
      (node (ref "U1") (pin "G6") (pinfunction "MGTAVCC_G11_G6") (pintype "power_in"))
      (node (ref "U1") (pin "J6") (pinfunction "MGTAVCC_G11_J6") (pintype "power_in"))
      (node (ref "U1") (pin "K12") (pinfunction "VCCINT_K12") (pintype "power_in"))
      (node (ref "U1") (pin "K14") (pinfunction "VCCINT_K14") (pintype "power_in"))
      (node (ref "U1") (pin "K16") (pinfunction "VCCINT_K16") (pintype "power_in"))
      (node (ref "U1") (pin "L11") (pinfunction "VCCINT_L11") (pintype "power_in"))
      (node (ref "U1") (pin "L13") (pinfunction "VCCINT_L13") (pintype "power_in"))
      (node (ref "U1") (pin "L15") (pinfunction "VCCINT_L15") (pintype "power_in"))
      (node (ref "U1") (pin "L6") (pinfunction "MGTAVCC_G11_L6") (pintype "power_in"))
      (node (ref "U1") (pin "M10") (pinfunction "VCCINT_M10") (pintype "power_in"))
      (node (ref "U1") (pin "M12") (pinfunction "VCCINT_M12") (pintype "power_in"))
      (node (ref "U1") (pin "M14") (pinfunction "VCCINT_M14") (pintype "power_in"))
      (node (ref "U1") (pin "N11") (pinfunction "VCCINT_N11") (pintype "power_in"))
      (node (ref "U1") (pin "N13") (pinfunction "VCCINT_N13") (pintype "power_in"))
      (node (ref "U1") (pin "N15") (pinfunction "VCCINT_N15") (pintype "power_in"))
      (node (ref "U1") (pin "N6") (pinfunction "MGTAVCC_G10_N6") (pintype "power_in"))
      (node (ref "U1") (pin "P10") (pinfunction "VCCINT_P10") (pintype "power_in"))
      (node (ref "U1") (pin "P14") (pinfunction "VCCINT_P14") (pintype "power_in"))
      (node (ref "U1") (pin "R11") (pinfunction "VCCINT_R11") (pintype "power_in"))
      (node (ref "U1") (pin "R15") (pinfunction "VCCBRAM_R15") (pintype "power_in"))
      (node (ref "U1") (pin "R6") (pinfunction "MGTAVCC_G10_R6") (pintype "power_in"))
      (node (ref "U1") (pin "T10") (pinfunction "VCCINT_T10") (pintype "power_in"))
      (node (ref "U1") (pin "T14") (pinfunction "VCCINT_T14") (pintype "power_in"))
      (node (ref "U1") (pin "U11") (pinfunction "VCCINT_U11") (pintype "power_in"))
      (node (ref "U1") (pin "U15") (pinfunction "VCCBRAM_U15") (pintype "power_in"))
      (node (ref "U1") (pin "U6") (pinfunction "MGTAVCC_G10_U6") (pintype "power_in"))
      (node (ref "U1") (pin "V10") (pinfunction "VCCINT_V10") (pintype "power_in"))
      (node (ref "U1") (pin "V12") (pinfunction "VCCINT_V12") (pintype "power_in"))
      (node (ref "U1") (pin "V14") (pinfunction "VCCINT_V14") (pintype "power_in"))
      (node (ref "U1") (pin "W11") (pinfunction "VCCINT_W11") (pintype "power_in"))
      (node (ref "U1") (pin "W13") (pinfunction "VCCINT_W13") (pintype "power_in"))
      (node (ref "U1") (pin "W15") (pinfunction "VCCBRAM_W15") (pintype "power_in"))
      (node (ref "U1") (pin "W6") (pinfunction "MGTAVCC_G10_W6") (pintype "power_in"))
      (node (ref "U1") (pin "Y10") (pinfunction "VCCINT_Y10") (pintype "power_in"))
      (node (ref "U1") (pin "Y12") (pinfunction "VCCINT_Y12") (pintype "power_in"))
      (node (ref "U1") (pin "Y14") (pinfunction "VCCINT_Y14") (pintype "power_in"))
      (node (ref "VR1") (pin "10") (pinfunction "VOUT_10") (pintype "passive"))
      (node (ref "VR1") (pin "11") (pinfunction "VOUT_11") (pintype "passive"))
      (node (ref "VR1") (pin "12") (pinfunction "VOUT_12") (pintype "passive"))
      (node (ref "VR1") (pin "13") (pinfunction "VOUT_13") (pintype "passive"))
      (node (ref "VR1") (pin "14") (pinfunction "VOUT_14") (pintype "passive"))
      (node (ref "VR1") (pin "15") (pinfunction "VOUT_15") (pintype "passive"))
      (node (ref "VR1") (pin "9") (pinfunction "VOUT_9") (pintype "passive"))
      (node (ref "VR2") (pin "10") (pinfunction "VOUT_10") (pintype "passive"))
      (node (ref "VR2") (pin "11") (pinfunction "VOUT_11") (pintype "passive"))
      (node (ref "VR2") (pin "12") (pinfunction "VOUT_12") (pintype "passive"))
      (node (ref "VR2") (pin "13") (pinfunction "VOUT_13") (pintype "passive"))
      (node (ref "VR2") (pin "14") (pinfunction "VOUT_14") (pintype "passive"))
      (node (ref "VR2") (pin "15") (pinfunction "VOUT_15") (pintype "passive"))
      (node (ref "VR2") (pin "9") (pinfunction "VOUT_9") (pintype "passive"))
    )
    (net (code "5") (name "1.2V") (class "Default")
      (node (ref "C129") (pin "2") (pinfunction "2_2") (pintype "passive"))
      (node (ref "C130") (pin "2") (pinfunction "2_2") (pintype "passive"))
      (node (ref "C131") (pin "2") (pinfunction "2_2") (pintype "passive"))
      (node (ref "C132") (pin "2") (pinfunction "2_2") (pintype "passive"))
      (node (ref "C133") (pin "2") (pinfunction "2_2") (pintype "passive"))
      (node (ref "C134") (pin "2") (pinfunction "2_2") (pintype "passive"))
      (node (ref "C135") (pin "2") (pinfunction "2_2") (pintype "passive"))
      (node (ref "C136") (pin "2") (pinfunction "2_2") (pintype "passive"))
      (node (ref "C137") (pin "2") (pinfunction "2_2") (pintype "passive"))
      (node (ref "C138") (pin "2") (pinfunction "2_2") (pintype "passive"))
      (node (ref "C47") (pin "1") (pinfunction "1_1") (pintype "passive"))
      (node (ref "C48") (pin "1") (pinfunction "1_1") (pintype "passive"))
      (node (ref "C49") (pin "1") (pinfunction "1_1") (pintype "passive"))
      (node (ref "C50") (pin "1") (pinfunction "1_1") (pintype "passive"))
      (node (ref "C51") (pin "1") (pinfunction "1_1") (pintype "passive"))
      (node (ref "R42") (pin "2") (pinfunction "2_2") (pintype "passive"))
      (node (ref "U1") (pin "AB3") (pinfunction "MGTAVTT_G10_AB3") (pintype "power_in"))
      (node (ref "U1") (pin "AC2") (pinfunction "MGTAVTT_G10_AC2") (pintype "power_in"))
      (node (ref "U1") (pin "AF3") (pinfunction "MGTAVTT_G10_AF3") (pintype "power_in"))
      (node (ref "U1") (pin "AG2") (pinfunction "MGTAVTT_G10_AG2") (pintype "power_in"))
      (node (ref "U1") (pin "AG9") (pinfunction "MGTAVTT_G10_AG9") (pintype "power_in"))
      (node (ref "U1") (pin "AJ6") (pinfunction "MGTAVTT_G10_AJ6") (pintype "power_in"))
      (node (ref "U1") (pin "AJ9") (pinfunction "MGTAVTT_G10_AJ9") (pintype "power_in"))
      (node (ref "U1") (pin "AK3") (pinfunction "MGTAVTT_G10_AK3") (pintype "power_in"))
      (node (ref "U1") (pin "AK7") (pinfunction "MGTAVTT_G10_AK7") (pintype "power_in"))
      (node (ref "U1") (pin "B3") (pinfunction "MGTAVTT_G11_B3") (pintype "power_in"))
      (node (ref "U1") (pin "B7") (pinfunction "MGTAVTT_G11_B7") (pintype "power_in"))
      (node (ref "U1") (pin "C2") (pinfunction "MGTAVTT_G11_C2") (pintype "power_in"))
      (node (ref "U1") (pin "C6") (pinfunction "MGTAVTT_G11_C6") (pintype "power_in"))
      (node (ref "U1") (pin "C9") (pinfunction "MGTAVTT_G11_C9") (pintype "power_in"))
      (node (ref "U1") (pin "E9") (pinfunction "MGTAVTT_G11_E9") (pintype "power_in"))
      (node (ref "U1") (pin "F3") (pinfunction "MGTAVTT_G11_F3") (pintype "power_in"))
      (node (ref "U1") (pin "G2") (pinfunction "MGTAVTT_G11_G2") (pintype "power_in"))
      (node (ref "U1") (pin "K3") (pinfunction "MGTAVTT_G11_K3") (pintype "power_in"))
      (node (ref "U1") (pin "L2") (pinfunction "MGTAVTT_G11_L2") (pintype "power_in"))
      (node (ref "U1") (pin "P3") (pinfunction "MGTAVTT_G10_P3") (pintype "power_in"))
      (node (ref "U1") (pin "R2") (pinfunction "MGTAVTT_G10_R2") (pintype "power_in"))
      (node (ref "U1") (pin "V3") (pinfunction "MGTAVTT_G10_V3") (pintype "power_in"))
      (node (ref "U1") (pin "W2") (pinfunction "MGTAVTT_G10_W2") (pintype "power_in"))
      (node (ref "VR3") (pin "10") (pinfunction "VOUT_10") (pintype "passive"))
      (node (ref "VR3") (pin "11") (pinfunction "VOUT_11") (pintype "passive"))
      (node (ref "VR3") (pin "12") (pinfunction "VOUT_12") (pintype "passive"))
      (node (ref "VR3") (pin "13") (pinfunction "VOUT_13") (pintype "passive"))
      (node (ref "VR3") (pin "14") (pinfunction "VOUT_14") (pintype "passive"))
      (node (ref "VR3") (pin "15") (pinfunction "VOUT_15") (pintype "passive"))
      (node (ref "VR3") (pin "9") (pinfunction "VOUT_9") (pintype "passive"))
    )
    (net (code "6") (name "1.8V") (class "Default")
      (node (ref "C149") (pin "2") (pinfunction "2_2") (pintype "passive"))
      (node (ref "C150") (pin "2") (pinfunction "2_2") (pintype "passive"))
      (node (ref "C151") (pin "2") (pinfunction "2_2") (pintype "passive"))
      (node (ref "C152") (pin "2") (pinfunction "2_2") (pintype "passive"))
      (node (ref "C153") (pin "2") (pinfunction "2_2") (pintype "passive"))
      (node (ref "C179") (pin "2") (pinfunction "2_2") (pintype "passive"))
      (node (ref "C180") (pin "2") (pinfunction "2_2") (pintype "passive"))
      (node (ref "C63") (pin "1") (pinfunction "1_1") (pintype "passive"))
      (node (ref "C64") (pin "1") (pinfunction "1_1") (pintype "passive"))
      (node (ref "C65") (pin "1") (pinfunction "1_1") (pintype "passive"))
      (node (ref "C66") (pin "1") (pinfunction "1_1") (pintype "passive"))
      (node (ref "C67") (pin "1") (pinfunction "1_1") (pintype "passive"))
      (node (ref "FB1") (pin "2") (pinfunction "2_2") (pintype "passive"))
      (node (ref "R50") (pin "2") (pinfunction "2_2") (pintype "passive"))
      (node (ref "U1") (pin "AA8") (pinfunction "MGTVCCAUX_G10_AA8") (pintype "power_in"))
      (node (ref "U1") (pin "K8") (pinfunction "MGTVCCAUX_G11_K8") (pintype "power_in"))
      (node (ref "U1") (pin "M16") (pinfunction "VCCAUX_M16") (pintype "power_in"))
      (node (ref "U1") (pin "P16") (pinfunction "VCCAUX_P16") (pintype "power_in"))
      (node (ref "U1") (pin "T16") (pinfunction "VCCAUX_T16") (pintype "power_in"))
      (node (ref "U1") (pin "V16") (pinfunction "VCCAUX_V16") (pintype "power_in"))
      (node (ref "U1") (pin "Y16") (pinfunction "VCCAUX_Y16") (pintype "power_in"))
      (node (ref "U1") (pin "Y7") (pinfunction "MGTVCCAUX_G10_Y7") (pintype "power_in"))
      (node (ref "VR5") (pin "10") (pinfunction "VOUT_10") (pintype "passive"))
      (node (ref "VR5") (pin "11") (pinfunction "VOUT_11") (pintype "passive"))
      (node (ref "VR5") (pin "12") (pinfunction "VOUT_12") (pintype "passive"))
      (node (ref "VR5") (pin "13") (pinfunction "VOUT_13") (pintype "passive"))
      (node (ref "VR5") (pin "14") (pinfunction "VOUT_14") (pintype "passive"))
      (node (ref "VR5") (pin "15") (pinfunction "VOUT_15") (pintype "passive"))
      (node (ref "VR5") (pin "9") (pinfunction "VOUT_9") (pintype "passive"))
    )
    (net (code "7") (name "1.35V") (class "Default")
      (node (ref "C139") (pin "2") (pinfunction "2_2") (pintype "passive"))
      (node (ref "C140") (pin "2") (pinfunction "2_2") (pintype "passive"))
      (node (ref "C141") (pin "2") (pinfunction "2_2") (pintype "passive"))
      (node (ref "C142") (pin "2") (pinfunction "2_2") (pintype "passive"))
      (node (ref "C143") (pin "2") (pinfunction "2_2") (pintype "passive"))
      (node (ref "C144") (pin "2") (pinfunction "2_2") (pintype "passive"))
      (node (ref "C145") (pin "2") (pinfunction "2_2") (pintype "passive"))
      (node (ref "C146") (pin "2") (pinfunction "2_2") (pintype "passive"))
      (node (ref "C147") (pin "2") (pinfunction "2_2") (pintype "passive"))
      (node (ref "C148") (pin "2") (pinfunction "2_2") (pintype "passive"))
      (node (ref "C191") (pin "2") (pinfunction "2_2") (pintype "passive"))
      (node (ref "C192") (pin "2") (pinfunction "2_2") (pintype "passive"))
      (node (ref "C193") (pin "2") (pinfunction "2_2") (pintype "passive"))
      (node (ref "C194") (pin "2") (pinfunction "2_2") (pintype "passive"))
      (node (ref "C195") (pin "2") (pinfunction "2_2") (pintype "passive"))
      (node (ref "C196") (pin "2") (pinfunction "2_2") (pintype "passive"))
      (node (ref "C197") (pin "2") (pinfunction "2_2") (pintype "passive"))
      (node (ref "C198") (pin "2") (pinfunction "2_2") (pintype "passive"))
      (node (ref "C199") (pin "2") (pinfunction "2_2") (pintype "passive"))
      (node (ref "C200") (pin "2") (pinfunction "2_2") (pintype "passive"))
      (node (ref "C55") (pin "1") (pinfunction "1_1") (pintype "passive"))
      (node (ref "C56") (pin "1") (pinfunction "1_1") (pintype "passive"))
      (node (ref "C57") (pin "1") (pinfunction "1_1") (pintype "passive"))
      (node (ref "C58") (pin "1") (pinfunction "1_1") (pintype "passive"))
      (node (ref "C59") (pin "1") (pinfunction "1_1") (pintype "passive"))
      (node (ref "R46") (pin "2") (pinfunction "2_2") (pintype "passive"))
      (node (ref "U1") (pin "A19") (pinfunction "VCCO_17_A19") (pintype "power_in"))
      (node (ref "U1") (pin "A29") (pinfunction "VCCO_16_A29") (pintype "power_in"))
      (node (ref "U1") (pin "AA19") (pinfunction "VCCO_11_AA19") (pintype "power_in"))
      (node (ref "U1") (pin "AA29") (pinfunction "VCCO_13_AA29") (pintype "power_in"))
      (node (ref "U1") (pin "AB16") (pinfunction "VCCO_11_AB16") (pintype "power_in"))
      (node (ref "U1") (pin "AB26") (pinfunction "VCCO_13_AB26") (pintype "power_in"))
      (node (ref "U1") (pin "AC23") (pinfunction "VCCO_12_AC23") (pintype "power_in"))
      (node (ref "U1") (pin "AD20") (pinfunction "VCCO_12_AD20") (pintype "power_in"))
      (node (ref "U1") (pin "AD30") (pinfunction "VCCO_13_AD30") (pintype "power_in"))
      (node (ref "U1") (pin "AE17") (pinfunction "VCCO_11_AE17") (pintype "power_in"))
      (node (ref "U1") (pin "AE27") (pinfunction "VCCO_13_AE27") (pintype "power_in"))
      (node (ref "U1") (pin "AF14") (pinfunction "VCCO_11_AF14") (pintype "power_in"))
      (node (ref "U1") (pin "AF24") (pinfunction "VCCO_12_AF24") (pintype "power_in"))
      (node (ref "U1") (pin "AG21") (pinfunction "VCCO_12_AG21") (pintype "power_in"))
      (node (ref "U1") (pin "AH18") (pinfunction "VCCO_11_AH18") (pintype "power_in"))
      (node (ref "U1") (pin "AH28") (pinfunction "VCCO_13_AH28") (pintype "power_in"))
      (node (ref "U1") (pin "AJ15") (pinfunction "VCCO_11_AJ15") (pintype "power_in"))
      (node (ref "U1") (pin "AJ25") (pinfunction "VCCO_12_AJ25") (pintype "power_in"))
      (node (ref "U1") (pin "AK22") (pinfunction "VCCO_12_AK22") (pintype "power_in"))
      (node (ref "U1") (pin "B26") (pinfunction "VCCO_16_B26") (pintype "power_in"))
      (node (ref "U1") (pin "C23") (pinfunction "VCCO_17_C23") (pintype "power_in"))
      (node (ref "U1") (pin "D20") (pinfunction "VCCO_17_D20") (pintype "power_in"))
      (node (ref "U1") (pin "D30") (pinfunction "VCCO_16_D30") (pintype "power_in"))
      (node (ref "U1") (pin "E27") (pinfunction "VCCO_16_E27") (pintype "power_in"))
      (node (ref "U1") (pin "F24") (pinfunction "VCCO_16_F24") (pintype "power_in"))
      (node (ref "U1") (pin "G21") (pinfunction "VCCO_17_G21") (pintype "power_in"))
      (node (ref "U1") (pin "H18") (pinfunction "VCCO_17_H18") (pintype "power_in"))
      (node (ref "U1") (pin "H28") (pinfunction "VCCO_16_H28") (pintype "power_in"))
      (node (ref "U1") (pin "J25") (pinfunction "VCCO_16_J25") (pintype "power_in"))
      (node (ref "U1") (pin "K22") (pinfunction "VCCO_17_K22") (pintype "power_in"))
      (node (ref "U1") (pin "L19") (pinfunction "VCCO_15_L19") (pintype "power_in"))
      (node (ref "U1") (pin "L29") (pinfunction "VCCO_15_L29") (pintype "power_in"))
      (node (ref "U1") (pin "M26") (pinfunction "VCCO_15_M26") (pintype "power_in"))
      (node (ref "U1") (pin "N23") (pinfunction "VCCO_15_N23") (pintype "power_in"))
      (node (ref "U1") (pin "P20") (pinfunction "VCCO_15_P20") (pintype "power_in"))
      (node (ref "U1") (pin "P30") (pinfunction "VCCO_15_P30") (pintype "power_in"))
      (node (ref "U1") (pin "W25") (pinfunction "VCCO_13_W25") (pintype "power_in"))
      (node (ref "U1") (pin "Y22") (pinfunction "VCCO_12_Y22") (pintype "power_in"))
      (node (ref "VR4") (pin "10") (pinfunction "VOUT_10") (pintype "passive"))
      (node (ref "VR4") (pin "11") (pinfunction "VOUT_11") (pintype "passive"))
      (node (ref "VR4") (pin "12") (pinfunction "VOUT_12") (pintype "passive"))
      (node (ref "VR4") (pin "13") (pinfunction "VOUT_13") (pintype "passive"))
      (node (ref "VR4") (pin "14") (pinfunction "VOUT_14") (pintype "passive"))
      (node (ref "VR4") (pin "15") (pinfunction "VOUT_15") (pintype "passive"))
      (node (ref "VR4") (pin "9") (pinfunction "VOUT_9") (pintype "passive"))
    )
    (net (code "8") (name "3.3V") (class "Default")
      (node (ref "C154") (pin "2") (pinfunction "2_2") (pintype "passive"))
      (node (ref "C155") (pin "2") (pinfunction "2_2") (pintype "passive"))
      (node (ref "C156") (pin "2") (pinfunction "2_2") (pintype "passive"))
      (node (ref "C157") (pin "2") (pinfunction "2_2") (pintype "passive"))
      (node (ref "C158") (pin "2") (pinfunction "2_2") (pintype "passive"))
      (node (ref "C159") (pin "2") (pinfunction "2_2") (pintype "passive"))
      (node (ref "C160") (pin "2") (pinfunction "2_2") (pintype "passive"))
      (node (ref "C161") (pin "2") (pinfunction "2_2") (pintype "passive"))
      (node (ref "C162") (pin "2") (pinfunction "2_2") (pintype "passive"))
      (node (ref "C163") (pin "2") (pinfunction "2_2") (pintype "passive"))
      (node (ref "C181") (pin "2") (pinfunction "2_2") (pintype "passive"))
      (node (ref "C182") (pin "2") (pinfunction "2_2") (pintype "passive"))
      (node (ref "C183") (pin "2") (pinfunction "2_2") (pintype "passive"))
      (node (ref "C184") (pin "2") (pinfunction "2_2") (pintype "passive"))
      (node (ref "C185") (pin "2") (pinfunction "2_2") (pintype "passive"))
      (node (ref "C186") (pin "2") (pinfunction "2_2") (pintype "passive"))
      (node (ref "C187") (pin "2") (pinfunction "2_2") (pintype "passive"))
      (node (ref "C188") (pin "2") (pinfunction "2_2") (pintype "passive"))
      (node (ref "C189") (pin "2") (pinfunction "2_2") (pintype "passive"))
      (node (ref "C190") (pin "2") (pinfunction "2_2") (pintype "passive"))
      (node (ref "C71") (pin "1") (pinfunction "1_1") (pintype "passive"))
      (node (ref "C72") (pin "1") (pinfunction "1_1") (pintype "passive"))
      (node (ref "C73") (pin "1") (pinfunction "1_1") (pintype "passive"))
      (node (ref "C74") (pin "1") (pinfunction "1_1") (pintype "passive"))
      (node (ref "C75") (pin "1") (pinfunction "1_1") (pintype "passive"))
      (node (ref "R54") (pin "2") (pinfunction "2_2") (pintype "passive"))
      (node (ref "R58") (pin "1") (pinfunction "1_1") (pintype "passive"))
      (node (ref "U1") (pin "B16") (pinfunction "VCCO_18_B16") (pintype "power_in"))
      (node (ref "U1") (pin "E17") (pinfunction "VCCO_18_E17") (pintype "power_in"))
      (node (ref "U1") (pin "F14") (pinfunction "VCCO_18_F14") (pintype "power_in"))
      (node (ref "U1") (pin "J10") (pinfunction "VCCO_0_J10") (pintype "power_in"))
      (node (ref "U1") (pin "J15") (pinfunction "VCCO_18_J15") (pintype "power_in"))
      (node (ref "U1") (pin "K11") (pinfunction "VCCO_0_K11") (pintype "power_in"))
      (node (ref "U1") (pin "R17") (pinfunction "VCCO_14_R17") (pintype "power_in"))
      (node (ref "U1") (pin "R27") (pinfunction "VCCO_14_R27") (pintype "power_in"))
      (node (ref "U1") (pin "T24") (pinfunction "VCCO_14_T24") (pintype "power_in"))
      (node (ref "U1") (pin "U21") (pinfunction "VCCO_14_U21") (pintype "power_in"))
      (node (ref "U1") (pin "V18") (pinfunction "VCCO_14_V18") (pintype "power_in"))
      (node (ref "U1") (pin "V28") (pinfunction "VCCO_14_V28") (pintype "power_in"))
      (node (ref "VR6") (pin "10") (pinfunction "VOUT_10") (pintype "passive"))
      (node (ref "VR6") (pin "11") (pinfunction "VOUT_11") (pintype "passive"))
      (node (ref "VR6") (pin "12") (pinfunction "VOUT_12") (pintype "passive"))
      (node (ref "VR6") (pin "13") (pinfunction "VOUT_13") (pintype "passive"))
      (node (ref "VR6") (pin "14") (pinfunction "VOUT_14") (pintype "passive"))
      (node (ref "VR6") (pin "15") (pinfunction "VOUT_15") (pintype "passive"))
      (node (ref "VR6") (pin "9") (pinfunction "VOUT_9") (pintype "passive"))
    )
    (net (code "9") (name "GND") (class "Default")
      (node (ref "C109") (pin "1") (pinfunction "1_1") (pintype "passive"))
      (node (ref "C110") (pin "1") (pinfunction "1_1") (pintype "passive"))
      (node (ref "C111") (pin "1") (pinfunction "1_1") (pintype "passive"))
      (node (ref "C112") (pin "1") (pinfunction "1_1") (pintype "passive"))
      (node (ref "C113") (pin "1") (pinfunction "1_1") (pintype "passive"))
      (node (ref "C114") (pin "1") (pinfunction "1_1") (pintype "passive"))
      (node (ref "C115") (pin "1") (pinfunction "1_1") (pintype "passive"))
      (node (ref "C116") (pin "1") (pinfunction "1_1") (pintype "passive"))
      (node (ref "C117") (pin "1") (pinfunction "1_1") (pintype "passive"))
      (node (ref "C118") (pin "1") (pinfunction "1_1") (pintype "passive"))
      (node (ref "C119") (pin "1") (pinfunction "1_1") (pintype "passive"))
      (node (ref "C120") (pin "1") (pinfunction "1_1") (pintype "passive"))
      (node (ref "C121") (pin "1") (pinfunction "1_1") (pintype "passive"))
      (node (ref "C122") (pin "1") (pinfunction "1_1") (pintype "passive"))
      (node (ref "C123") (pin "1") (pinfunction "1_1") (pintype "passive"))
      (node (ref "C124") (pin "1") (pinfunction "1_1") (pintype "passive"))
      (node (ref "C125") (pin "1") (pinfunction "1_1") (pintype "passive"))
      (node (ref "C126") (pin "1") (pinfunction "1_1") (pintype "passive"))
      (node (ref "C127") (pin "1") (pinfunction "1_1") (pintype "passive"))
      (node (ref "C128") (pin "1") (pinfunction "1_1") (pintype "passive"))
      (node (ref "C129") (pin "1") (pinfunction "1_1") (pintype "passive"))
      (node (ref "C130") (pin "1") (pinfunction "1_1") (pintype "passive"))
      (node (ref "C131") (pin "1") (pinfunction "1_1") (pintype "passive"))
      (node (ref "C132") (pin "1") (pinfunction "1_1") (pintype "passive"))
      (node (ref "C133") (pin "1") (pinfunction "1_1") (pintype "passive"))
      (node (ref "C134") (pin "1") (pinfunction "1_1") (pintype "passive"))
      (node (ref "C135") (pin "1") (pinfunction "1_1") (pintype "passive"))
      (node (ref "C136") (pin "1") (pinfunction "1_1") (pintype "passive"))
      (node (ref "C137") (pin "1") (pinfunction "1_1") (pintype "passive"))
      (node (ref "C138") (pin "1") (pinfunction "1_1") (pintype "passive"))
      (node (ref "C139") (pin "1") (pinfunction "1_1") (pintype "passive"))
      (node (ref "C140") (pin "1") (pinfunction "1_1") (pintype "passive"))
      (node (ref "C141") (pin "1") (pinfunction "1_1") (pintype "passive"))
      (node (ref "C142") (pin "1") (pinfunction "1_1") (pintype "passive"))
      (node (ref "C143") (pin "1") (pinfunction "1_1") (pintype "passive"))
      (node (ref "C144") (pin "1") (pinfunction "1_1") (pintype "passive"))
      (node (ref "C145") (pin "1") (pinfunction "1_1") (pintype "passive"))
      (node (ref "C146") (pin "1") (pinfunction "1_1") (pintype "passive"))
      (node (ref "C147") (pin "1") (pinfunction "1_1") (pintype "passive"))
      (node (ref "C148") (pin "1") (pinfunction "1_1") (pintype "passive"))
      (node (ref "C149") (pin "1") (pinfunction "1_1") (pintype "passive"))
      (node (ref "C150") (pin "1") (pinfunction "1_1") (pintype "passive"))
      (node (ref "C151") (pin "1") (pinfunction "1_1") (pintype "passive"))
      (node (ref "C152") (pin "1") (pinfunction "1_1") (pintype "passive"))
      (node (ref "C153") (pin "1") (pinfunction "1_1") (pintype "passive"))
      (node (ref "C154") (pin "1") (pinfunction "1_1") (pintype "passive"))
      (node (ref "C155") (pin "1") (pinfunction "1_1") (pintype "passive"))
      (node (ref "C156") (pin "1") (pinfunction "1_1") (pintype "passive"))
      (node (ref "C157") (pin "1") (pinfunction "1_1") (pintype "passive"))
      (node (ref "C158") (pin "1") (pinfunction "1_1") (pintype "passive"))
      (node (ref "C159") (pin "1") (pinfunction "1_1") (pintype "passive"))
      (node (ref "C160") (pin "1") (pinfunction "1_1") (pintype "passive"))
      (node (ref "C161") (pin "1") (pinfunction "1_1") (pintype "passive"))
      (node (ref "C162") (pin "1") (pinfunction "1_1") (pintype "passive"))
      (node (ref "C163") (pin "1") (pinfunction "1_1") (pintype "passive"))
      (node (ref "C179") (pin "1") (pinfunction "1_1") (pintype "passive"))
      (node (ref "C180") (pin "1") (pinfunction "1_1") (pintype "passive"))
      (node (ref "C181") (pin "1") (pinfunction "1_1") (pintype "passive"))
      (node (ref "C182") (pin "1") (pinfunction "1_1") (pintype "passive"))
      (node (ref "C183") (pin "1") (pinfunction "1_1") (pintype "passive"))
      (node (ref "C184") (pin "1") (pinfunction "1_1") (pintype "passive"))
      (node (ref "C185") (pin "1") (pinfunction "1_1") (pintype "passive"))
      (node (ref "C186") (pin "1") (pinfunction "1_1") (pintype "passive"))
      (node (ref "C187") (pin "1") (pinfunction "1_1") (pintype "passive"))
      (node (ref "C188") (pin "1") (pinfunction "1_1") (pintype "passive"))
      (node (ref "C189") (pin "1") (pinfunction "1_1") (pintype "passive"))
      (node (ref "C190") (pin "1") (pinfunction "1_1") (pintype "passive"))
      (node (ref "C191") (pin "1") (pinfunction "1_1") (pintype "passive"))
      (node (ref "C192") (pin "1") (pinfunction "1_1") (pintype "passive"))
      (node (ref "C193") (pin "1") (pinfunction "1_1") (pintype "passive"))
      (node (ref "C194") (pin "1") (pinfunction "1_1") (pintype "passive"))
      (node (ref "C195") (pin "1") (pinfunction "1_1") (pintype "passive"))
      (node (ref "C196") (pin "1") (pinfunction "1_1") (pintype "passive"))
      (node (ref "C197") (pin "1") (pinfunction "1_1") (pintype "passive"))
      (node (ref "C198") (pin "1") (pinfunction "1_1") (pintype "passive"))
      (node (ref "C199") (pin "1") (pinfunction "1_1") (pintype "passive"))
      (node (ref "C200") (pin "1") (pinfunction "1_1") (pintype "passive"))
      (node (ref "C34") (pin "1") (pinfunction "1_1") (pintype "passive"))
      (node (ref "C35") (pin "1") (pinfunction "1_1") (pintype "passive"))
      (node (ref "C37") (pin "2") (pinfunction "2_2") (pintype "passive"))
      (node (ref "C38") (pin "2") (pinfunction "2_2") (pintype "passive"))
      (node (ref "C39") (pin "2") (pinfunction "2_2") (pintype "passive"))
      (node (ref "C40") (pin "2") (pinfunction "2_2") (pintype "passive"))
      (node (ref "C41") (pin "1") (pinfunction "1_1") (pintype "passive"))
      (node (ref "C42") (pin "1") (pinfunction "1_1") (pintype "passive"))
      (node (ref "C43") (pin "1") (pinfunction "1_1") (pintype "passive"))
      (node (ref "C44") (pin "1") (pinfunction "1_1") (pintype "passive"))
      (node (ref "C45") (pin "1") (pinfunction "1_1") (pintype "passive"))
      (node (ref "C46") (pin "1") (pinfunction "1_1") (pintype "passive"))
      (node (ref "C48") (pin "2") (pinfunction "2_2") (pintype "passive"))
      (node (ref "C49") (pin "2") (pinfunction "2_2") (pintype "passive"))
      (node (ref "C50") (pin "2") (pinfunction "2_2") (pintype "passive"))
      (node (ref "C51") (pin "2") (pinfunction "2_2") (pintype "passive"))
      (node (ref "C52") (pin "1") (pinfunction "1_1") (pintype "passive"))
      (node (ref "C53") (pin "1") (pinfunction "1_1") (pintype "passive"))
      (node (ref "C54") (pin "1") (pinfunction "1_1") (pintype "passive"))
      (node (ref "C56") (pin "2") (pinfunction "2_2") (pintype "passive"))
      (node (ref "C57") (pin "2") (pinfunction "2_2") (pintype "passive"))
      (node (ref "C58") (pin "2") (pinfunction "2_2") (pintype "passive"))
      (node (ref "C59") (pin "2") (pinfunction "2_2") (pintype "passive"))
      (node (ref "C60") (pin "1") (pinfunction "1_1") (pintype "passive"))
      (node (ref "C61") (pin "1") (pinfunction "1_1") (pintype "passive"))
      (node (ref "C62") (pin "1") (pinfunction "1_1") (pintype "passive"))
      (node (ref "C64") (pin "2") (pinfunction "2_2") (pintype "passive"))
      (node (ref "C65") (pin "2") (pinfunction "2_2") (pintype "passive"))
      (node (ref "C66") (pin "2") (pinfunction "2_2") (pintype "passive"))
      (node (ref "C67") (pin "2") (pinfunction "2_2") (pintype "passive"))
      (node (ref "C68") (pin "1") (pinfunction "1_1") (pintype "passive"))
      (node (ref "C69") (pin "1") (pinfunction "1_1") (pintype "passive"))
      (node (ref "C70") (pin "1") (pinfunction "1_1") (pintype "passive"))
      (node (ref "C72") (pin "2") (pinfunction "2_2") (pintype "passive"))
      (node (ref "C73") (pin "2") (pinfunction "2_2") (pintype "passive"))
      (node (ref "C74") (pin "2") (pinfunction "2_2") (pintype "passive"))
      (node (ref "C75") (pin "2") (pinfunction "2_2") (pintype "passive"))
      (node (ref "C76") (pin "1") (pinfunction "1_1") (pintype "passive"))
      (node (ref "C77") (pin "2") (pinfunction "2_2") (pintype "passive"))
      (node (ref "C78") (pin "2") (pinfunction "2_2") (pintype "passive"))
      (node (ref "C79") (pin "2") (pinfunction "2_2") (pintype "passive"))
      (node (ref "C80") (pin "2") (pinfunction "2_2") (pintype "passive"))
      (node (ref "R36") (pin "2") (pinfunction "2_2") (pintype "passive"))
      (node (ref "R38") (pin "2") (pinfunction "2_2") (pintype "passive"))
      (node (ref "R40") (pin "2") (pinfunction "2_2") (pintype "passive"))
      (node (ref "R43") (pin "2") (pinfunction "2_2") (pintype "passive"))
      (node (ref "R44") (pin "2") (pinfunction "2_2") (pintype "passive"))
      (node (ref "R47") (pin "2") (pinfunction "2_2") (pintype "passive"))
      (node (ref "R48") (pin "2") (pinfunction "2_2") (pintype "passive"))
      (node (ref "R51") (pin "2") (pinfunction "2_2") (pintype "passive"))
      (node (ref "R52") (pin "2") (pinfunction "2_2") (pintype "passive"))
      (node (ref "R55") (pin "2") (pinfunction "2_2") (pintype "passive"))
      (node (ref "R56") (pin "2") (pinfunction "2_2") (pintype "passive"))
      (node (ref "R59") (pin "2") (pinfunction "2_2") (pintype "passive"))
      (node (ref "U1") (pin "A1") (pinfunction "GND_A1") (pintype "power_in"))
      (node (ref "U1") (pin "A10") (pinfunction "GND_A10") (pintype "power_in"))
      (node (ref "U1") (pin "A13") (pinfunction "GND_A13") (pintype "power_in"))
      (node (ref "U1") (pin "A2") (pinfunction "GND_A2") (pintype "power_in"))
      (node (ref "U1") (pin "A24") (pinfunction "GND_A24") (pintype "power_in"))
      (node (ref "U1") (pin "A5") (pinfunction "GND_A5") (pintype "power_in"))
      (node (ref "U1") (pin "A6") (pinfunction "GND_A6") (pintype "power_in"))
      (node (ref "U1") (pin "A9") (pinfunction "GND_A9") (pintype "power_in"))
      (node (ref "U1") (pin "AA1") (pinfunction "GND_AA1") (pintype "power_in"))
      (node (ref "U1") (pin "AA10") (pinfunction "GND_AA10") (pintype "power_in"))
      (node (ref "U1") (pin "AA12") (pinfunction "GND_AA12") (pintype "power_in"))
      (node (ref "U1") (pin "AA14") (pinfunction "GND_AA14") (pintype "power_in"))
      (node (ref "U1") (pin "AA16") (pinfunction "GND_AA16") (pintype "power_in"))
      (node (ref "U1") (pin "AA2") (pinfunction "GND_AA2") (pintype "power_in"))
      (node (ref "U1") (pin "AA24") (pinfunction "GND_AA24") (pintype "power_in"))
      (node (ref "U1") (pin "AA5") (pinfunction "GND_AA5") (pintype "power_in"))
      (node (ref "U1") (pin "AA7") (pinfunction "GND_AA7") (pintype "power_in"))
      (node (ref "U1") (pin "AA9") (pinfunction "GND_AA9") (pintype "power_in"))
      (node (ref "U1") (pin "AB10") (pinfunction "GND_AB10") (pintype "power_in"))
      (node (ref "U1") (pin "AB13") (pinfunction "GND_AB13") (pintype "power_in"))
      (node (ref "U1") (pin "AB21") (pinfunction "GND_AB21") (pintype "power_in"))
      (node (ref "U1") (pin "AB4") (pinfunction "GND_AB4") (pintype "power_in"))
      (node (ref "U1") (pin "AB7") (pinfunction "GND_AB7") (pintype "power_in"))
      (node (ref "U1") (pin "AB8") (pinfunction "GND_AB8") (pintype "power_in"))
      (node (ref "U1") (pin "AB9") (pinfunction "GND_AB9") (pintype "power_in"))
      (node (ref "U1") (pin "AC1") (pinfunction "GND_AC1") (pintype "power_in"))
      (node (ref "U1") (pin "AC18") (pinfunction "GND_AC18") (pintype "power_in"))
      (node (ref "U1") (pin "AC28") (pinfunction "GND_AC28") (pintype "power_in"))
      (node (ref "U1") (pin "AC5") (pinfunction "GND_AC5") (pintype "power_in"))
      (node (ref "U1") (pin "AC9") (pinfunction "GND_AC9") (pintype "power_in"))
      (node (ref "U1") (pin "AD10") (pinfunction "GND_AD10") (pintype "power_in"))
      (node (ref "U1") (pin "AD11") (pinfunction "GND_AD11") (pintype "power_in"))
      (node (ref "U1") (pin "AD12") (pinfunction "GND_AD12") (pintype "power_in"))
      (node (ref "U1") (pin "AD13") (pinfunction "GND_AD13") (pintype "power_in"))
      (node (ref "U1") (pin "AD15") (pinfunction "GND_AD15") (pintype "power_in"))
      (node (ref "U1") (pin "AD25") (pinfunction "GND_AD25") (pintype "power_in"))
      (node (ref "U1") (pin "AD3") (pinfunction "GND_AD3") (pintype "power_in"))
      (node (ref "U1") (pin "AD4") (pinfunction "GND_AD4") (pintype "power_in"))
      (node (ref "U1") (pin "AD7") (pinfunction "GND_AD7") (pintype "power_in"))
      (node (ref "U1") (pin "AD8") (pinfunction "GND_AD8") (pintype "power_in"))
      (node (ref "U1") (pin "AD9") (pinfunction "GND_AD9") (pintype "power_in"))
      (node (ref "U1") (pin "AE1") (pinfunction "GND_AE1") (pintype "power_in"))
      (node (ref "U1") (pin "AE10") (pinfunction "GND_AE10") (pintype "power_in"))
      (node (ref "U1") (pin "AE13") (pinfunction "GND_AE13") (pintype "power_in"))
      (node (ref "U1") (pin "AE2") (pinfunction "GND_AE2") (pintype "power_in"))
      (node (ref "U1") (pin "AE22") (pinfunction "GND_AE22") (pintype "power_in"))
      (node (ref "U1") (pin "AE5") (pinfunction "GND_AE5") (pintype "power_in"))
      (node (ref "U1") (pin "AE9") (pinfunction "GND_AE9") (pintype "power_in"))
      (node (ref "U1") (pin "AF11") (pinfunction "GND_AF11") (pintype "power_in"))
      (node (ref "U1") (pin "AF12") (pinfunction "GND_AF12") (pintype "power_in"))
      (node (ref "U1") (pin "AF13") (pinfunction "GND_AF13") (pintype "power_in"))
      (node (ref "U1") (pin "AF19") (pinfunction "GND_AF19") (pintype "power_in"))
      (node (ref "U1") (pin "AF29") (pinfunction "GND_AF29") (pintype "power_in"))
      (node (ref "U1") (pin "AF4") (pinfunction "GND_AF4") (pintype "power_in"))
      (node (ref "U1") (pin "AF7") (pinfunction "GND_AF7") (pintype "power_in"))
      (node (ref "U1") (pin "AF8") (pinfunction "GND_AF8") (pintype "power_in"))
      (node (ref "U1") (pin "AG1") (pinfunction "GND_AG1") (pintype "power_in"))
      (node (ref "U1") (pin "AG10") (pinfunction "GND_AG10") (pintype "power_in"))
      (node (ref "U1") (pin "AG13") (pinfunction "GND_AG13") (pintype "power_in"))
      (node (ref "U1") (pin "AG16") (pinfunction "GND_AG16") (pintype "power_in"))
      (node (ref "U1") (pin "AG26") (pinfunction "GND_AG26") (pintype "power_in"))
      (node (ref "U1") (pin "AG5") (pinfunction "GND_AG5") (pintype "power_in"))
      (node (ref "U1") (pin "AH12") (pinfunction "GND_AH12") (pintype "power_in"))
      (node (ref "U1") (pin "AH13") (pinfunction "GND_AH13") (pintype "power_in"))
      (node (ref "U1") (pin "AH23") (pinfunction "GND_AH23") (pintype "power_in"))
      (node (ref "U1") (pin "AH3") (pinfunction "GND_AH3") (pintype "power_in"))
      (node (ref "U1") (pin "AH4") (pinfunction "GND_AH4") (pintype "power_in"))
      (node (ref "U1") (pin "AH8") (pinfunction "GND_AH8") (pintype "power_in"))
      (node (ref "U1") (pin "AJ1") (pinfunction "GND_AJ1") (pintype "power_in"))
      (node (ref "U1") (pin "AJ10") (pinfunction "GND_AJ10") (pintype "power_in"))
      (node (ref "U1") (pin "AJ13") (pinfunction "GND_AJ13") (pintype "power_in"))
      (node (ref "U1") (pin "AJ2") (pinfunction "GND_AJ2") (pintype "power_in"))
      (node (ref "U1") (pin "AJ20") (pinfunction "GND_AJ20") (pintype "power_in"))
      (node (ref "U1") (pin "AJ30") (pinfunction "GND_AJ30") (pintype "power_in"))
      (node (ref "U1") (pin "AJ5") (pinfunction "GND_AJ5") (pintype "power_in"))
      (node (ref "U1") (pin "AK12") (pinfunction "GND_AK12") (pintype "power_in"))
      (node (ref "U1") (pin "AK13") (pinfunction "GND_AK13") (pintype "power_in"))
      (node (ref "U1") (pin "AK17") (pinfunction "GND_AK17") (pintype "power_in"))
      (node (ref "U1") (pin "AK27") (pinfunction "GND_AK27") (pintype "power_in"))
      (node (ref "U1") (pin "AK4") (pinfunction "GND_AK4") (pintype "power_in"))
      (node (ref "U1") (pin "AK8") (pinfunction "GND_AK8") (pintype "power_in"))
      (node (ref "U1") (pin "B12") (pinfunction "GND_B12") (pintype "power_in"))
      (node (ref "U1") (pin "B13") (pinfunction "GND_B13") (pintype "power_in"))
      (node (ref "U1") (pin "B21") (pinfunction "GND_B21") (pintype "power_in"))
      (node (ref "U1") (pin "B4") (pinfunction "GND_B4") (pintype "power_in"))
      (node (ref "U1") (pin "B8") (pinfunction "GND_B8") (pintype "power_in"))
      (node (ref "U1") (pin "C1") (pinfunction "GND_C1") (pintype "power_in"))
      (node (ref "U1") (pin "C10") (pinfunction "GND_C10") (pintype "power_in"))
      (node (ref "U1") (pin "C13") (pinfunction "GND_C13") (pintype "power_in"))
      (node (ref "U1") (pin "C18") (pinfunction "GND_C18") (pintype "power_in"))
      (node (ref "U1") (pin "C28") (pinfunction "GND_C28") (pintype "power_in"))
      (node (ref "U1") (pin "C5") (pinfunction "GND_C5") (pintype "power_in"))
      (node (ref "U1") (pin "D12") (pinfunction "GND_D12") (pintype "power_in"))
      (node (ref "U1") (pin "D13") (pinfunction "GND_D13") (pintype "power_in"))
      (node (ref "U1") (pin "D15") (pinfunction "GND_D15") (pintype "power_in"))
      (node (ref "U1") (pin "D25") (pinfunction "GND_D25") (pintype "power_in"))
      (node (ref "U1") (pin "D3") (pinfunction "GND_D3") (pintype "power_in"))
      (node (ref "U1") (pin "D4") (pinfunction "GND_D4") (pintype "power_in"))
      (node (ref "U1") (pin "D8") (pinfunction "GND_D8") (pintype "power_in"))
      (node (ref "U1") (pin "E1") (pinfunction "GND_E1") (pintype "power_in"))
      (node (ref "U1") (pin "E10") (pinfunction "GND_E10") (pintype "power_in"))
      (node (ref "U1") (pin "E13") (pinfunction "GND_E13") (pintype "power_in"))
      (node (ref "U1") (pin "E2") (pinfunction "GND_E2") (pintype "power_in"))
      (node (ref "U1") (pin "E22") (pinfunction "GND_E22") (pintype "power_in"))
      (node (ref "U1") (pin "E5") (pinfunction "GND_E5") (pintype "power_in"))
      (node (ref "U1") (pin "F11") (pinfunction "GND_F11") (pintype "power_in"))
      (node (ref "U1") (pin "F12") (pinfunction "GND_F12") (pintype "power_in"))
      (node (ref "U1") (pin "F13") (pinfunction "GND_F13") (pintype "power_in"))
      (node (ref "U1") (pin "F19") (pinfunction "GND_F19") (pintype "power_in"))
      (node (ref "U1") (pin "F29") (pinfunction "GND_F29") (pintype "power_in"))
      (node (ref "U1") (pin "F4") (pinfunction "GND_F4") (pintype "power_in"))
      (node (ref "U1") (pin "F7") (pinfunction "GND_F7") (pintype "power_in"))
      (node (ref "U1") (pin "F8") (pinfunction "GND_F8") (pintype "power_in"))
      (node (ref "U1") (pin "G1") (pinfunction "GND_G1") (pintype "power_in"))
      (node (ref "U1") (pin "G10") (pinfunction "GND_G10") (pintype "power_in"))
      (node (ref "U1") (pin "G11") (pinfunction "GND_G11") (pintype "power_in"))
      (node (ref "U1") (pin "G12") (pinfunction "GND_G12") (pintype "power_in"))
      (node (ref "U1") (pin "G16") (pinfunction "GND_G16") (pintype "power_in"))
      (node (ref "U1") (pin "G26") (pinfunction "GND_G26") (pintype "power_in"))
      (node (ref "U1") (pin "G5") (pinfunction "GND_G5") (pintype "power_in"))
      (node (ref "U1") (pin "G9") (pinfunction "GND_G9") (pintype "power_in"))
      (node (ref "U1") (pin "H23") (pinfunction "GND_H23") (pintype "power_in"))
      (node (ref "U1") (pin "H3") (pinfunction "GND_H3") (pintype "power_in"))
      (node (ref "U1") (pin "H4") (pinfunction "GND_H4") (pintype "power_in"))
      (node (ref "U1") (pin "H7") (pinfunction "GND_H7") (pintype "power_in"))
      (node (ref "U1") (pin "H8") (pinfunction "GND_H8") (pintype "power_in"))
      (node (ref "U1") (pin "H9") (pinfunction "GND_H9") (pintype "power_in"))
      (node (ref "U1") (pin "J1") (pinfunction "GND_J1") (pintype "power_in"))
      (node (ref "U1") (pin "J12") (pinfunction "GND_J12") (pintype "power_in"))
      (node (ref "U1") (pin "J2") (pinfunction "GND_J2") (pintype "power_in"))
      (node (ref "U1") (pin "J20") (pinfunction "GND_J20") (pintype "power_in"))
      (node (ref "U1") (pin "J30") (pinfunction "GND_J30") (pintype "power_in"))
      (node (ref "U1") (pin "J5") (pinfunction "GND_J5") (pintype "power_in"))
      (node (ref "U1") (pin "J9") (pinfunction "GND_J9") (pintype "power_in"))
      (node (ref "U1") (pin "K10") (pinfunction "GND_K10") (pintype "power_in"))
      (node (ref "U1") (pin "K13") (pinfunction "GND_K13") (pintype "power_in"))
      (node (ref "U1") (pin "K15") (pinfunction "GND_K15") (pintype "power_in"))
      (node (ref "U1") (pin "K17") (pinfunction "GND_K17") (pintype "power_in"))
      (node (ref "U1") (pin "K27") (pinfunction "GND_K27") (pintype "power_in"))
      (node (ref "U1") (pin "K4") (pinfunction "GND_K4") (pintype "power_in"))
      (node (ref "U1") (pin "K7") (pinfunction "GND_K7") (pintype "power_in"))
      (node (ref "U1") (pin "K9") (pinfunction "GND_K9") (pintype "power_in"))
      (node (ref "U1") (pin "L1") (pinfunction "GND_L1") (pintype "power_in"))
      (node (ref "U1") (pin "L10") (pinfunction "GND_L10") (pintype "power_in"))
      (node (ref "U1") (pin "L12") (pinfunction "GND_L12") (pintype "power_in"))
      (node (ref "U1") (pin "L14") (pinfunction "GND_L14") (pintype "power_in"))
      (node (ref "U1") (pin "L16") (pinfunction "GND_L16") (pintype "power_in"))
      (node (ref "U1") (pin "L24") (pinfunction "GND_L24") (pintype "power_in"))
      (node (ref "U1") (pin "L5") (pinfunction "GND_L5") (pintype "power_in"))
      (node (ref "U1") (pin "L9") (pinfunction "GND_L9") (pintype "power_in"))
      (node (ref "U1") (pin "M11") (pinfunction "GND_M11") (pintype "power_in"))
      (node (ref "U1") (pin "M13") (pinfunction "GND_M13") (pintype "power_in"))
      (node (ref "U1") (pin "M15") (pinfunction "GND_M15") (pintype "power_in"))
      (node (ref "U1") (pin "M21") (pinfunction "GND_M21") (pintype "power_in"))
      (node (ref "U1") (pin "M3") (pinfunction "GND_M3") (pintype "power_in"))
      (node (ref "U1") (pin "M4") (pinfunction "GND_M4") (pintype "power_in"))
      (node (ref "U1") (pin "M7") (pinfunction "GND_M7") (pintype "power_in"))
      (node (ref "U1") (pin "M8") (pinfunction "GND_M8") (pintype "power_in"))
      (node (ref "U1") (pin "M9") (pinfunction "GND_M9") (pintype "power_in"))
      (node (ref "U1") (pin "N1") (pinfunction "GND_N1") (pintype "power_in"))
      (node (ref "U1") (pin "N10") (pinfunction "GND_N10") (pintype "power_in"))
      (node (ref "U1") (pin "N12") (pinfunction "GND_N12") (pintype "power_in"))
      (node (ref "U1") (pin "N14") (pinfunction "GND_N14") (pintype "power_in"))
      (node (ref "U1") (pin "N16") (pinfunction "GND_N16") (pintype "power_in"))
      (node (ref "U1") (pin "N18") (pinfunction "GND_N18") (pintype "power_in"))
      (node (ref "U1") (pin "N2") (pinfunction "GND_N2") (pintype "power_in"))
      (node (ref "U1") (pin "N28") (pinfunction "GND_N28") (pintype "power_in"))
      (node (ref "U1") (pin "N5") (pinfunction "GND_N5") (pintype "power_in"))
      (node (ref "U1") (pin "N9") (pinfunction "GND_N9") (pintype "power_in"))
      (node (ref "U1") (pin "P11") (pinfunction "GND_P11") (pintype "power_in"))
      (node (ref "U1") (pin "P12") (pinfunction "GNDADC_0_P12") (pintype "power_in"))
      (node (ref "U1") (pin "P15") (pinfunction "GND_P15") (pintype "power_in"))
      (node (ref "U1") (pin "P25") (pinfunction "GND_P25") (pintype "power_in"))
      (node (ref "U1") (pin "P4") (pinfunction "GND_P4") (pintype "power_in"))
      (node (ref "U1") (pin "P7") (pinfunction "GND_P7") (pintype "power_in"))
      (node (ref "U1") (pin "P8") (pinfunction "GND_P8") (pintype "power_in"))
      (node (ref "U1") (pin "P9") (pinfunction "GND_P9") (pintype "power_in"))
      (node (ref "U1") (pin "R1") (pinfunction "GND_R1") (pintype "power_in"))
      (node (ref "U1") (pin "R10") (pinfunction "GND_R10") (pintype "power_in"))
      (node (ref "U1") (pin "R14") (pinfunction "GND_R14") (pintype "power_in"))
      (node (ref "U1") (pin "R16") (pinfunction "GND_R16") (pintype "power_in"))
      (node (ref "U1") (pin "R22") (pinfunction "GND_R22") (pintype "power_in"))
      (node (ref "U1") (pin "R5") (pinfunction "GND_R5") (pintype "power_in"))
      (node (ref "U1") (pin "R9") (pinfunction "GND_R9") (pintype "power_in"))
      (node (ref "U1") (pin "T11") (pinfunction "GND_T11") (pintype "power_in"))
      (node (ref "U1") (pin "T15") (pinfunction "GND_T15") (pintype "power_in"))
      (node (ref "U1") (pin "T19") (pinfunction "GND_T19") (pintype "power_in"))
      (node (ref "U1") (pin "T29") (pinfunction "GND_T29") (pintype "power_in"))
      (node (ref "U1") (pin "T3") (pinfunction "GND_T3") (pintype "power_in"))
      (node (ref "U1") (pin "T4") (pinfunction "GND_T4") (pintype "power_in"))
      (node (ref "U1") (pin "T7") (pinfunction "GND_T7") (pintype "power_in"))
      (node (ref "U1") (pin "T8") (pinfunction "GND_T8") (pintype "power_in"))
      (node (ref "U1") (pin "T9") (pinfunction "GND_T9") (pintype "power_in"))
      (node (ref "U1") (pin "U1") (pinfunction "GND_U1") (pintype "power_in"))
      (node (ref "U1") (pin "U10") (pinfunction "GND_U10") (pintype "power_in"))
      (node (ref "U1") (pin "U14") (pinfunction "GND_U14") (pintype "power_in"))
      (node (ref "U1") (pin "U16") (pinfunction "GND_U16") (pintype "power_in"))
      (node (ref "U1") (pin "U2") (pinfunction "GND_U2") (pintype "power_in"))
      (node (ref "U1") (pin "U26") (pinfunction "GND_U26") (pintype "power_in"))
      (node (ref "U1") (pin "U5") (pinfunction "GND_U5") (pintype "power_in"))
      (node (ref "U1") (pin "U9") (pinfunction "GND_U9") (pintype "power_in"))
      (node (ref "U1") (pin "V11") (pinfunction "GND_V11") (pintype "power_in"))
      (node (ref "U1") (pin "V13") (pinfunction "GND_V13") (pintype "power_in"))
      (node (ref "U1") (pin "V15") (pinfunction "GND_V15") (pintype "power_in"))
      (node (ref "U1") (pin "V23") (pinfunction "GND_V23") (pintype "power_in"))
      (node (ref "U1") (pin "V4") (pinfunction "GND_V4") (pintype "power_in"))
      (node (ref "U1") (pin "V7") (pinfunction "GND_V7") (pintype "power_in"))
      (node (ref "U1") (pin "V8") (pinfunction "GND_V8") (pintype "power_in"))
      (node (ref "U1") (pin "V9") (pinfunction "GND_V9") (pintype "power_in"))
      (node (ref "U1") (pin "W1") (pinfunction "GND_W1") (pintype "power_in"))
      (node (ref "U1") (pin "W10") (pinfunction "GND_W10") (pintype "power_in"))
      (node (ref "U1") (pin "W12") (pinfunction "GND_W12") (pintype "power_in"))
      (node (ref "U1") (pin "W14") (pinfunction "GND_W14") (pintype "power_in"))
      (node (ref "U1") (pin "W16") (pinfunction "GND_W16") (pintype "power_in"))
      (node (ref "U1") (pin "W20") (pinfunction "GND_W20") (pintype "power_in"))
      (node (ref "U1") (pin "W30") (pinfunction "GND_W30") (pintype "power_in"))
      (node (ref "U1") (pin "W5") (pinfunction "GND_W5") (pintype "power_in"))
      (node (ref "U1") (pin "W9") (pinfunction "GND_W9") (pintype "power_in"))
      (node (ref "U1") (pin "Y11") (pinfunction "GND_Y11") (pintype "power_in"))
      (node (ref "U1") (pin "Y13") (pinfunction "GND_Y13") (pintype "power_in"))
      (node (ref "U1") (pin "Y15") (pinfunction "GND_Y15") (pintype "power_in"))
      (node (ref "U1") (pin "Y17") (pinfunction "GND_Y17") (pintype "power_in"))
      (node (ref "U1") (pin "Y27") (pinfunction "GND_Y27") (pintype "power_in"))
      (node (ref "U1") (pin "Y3") (pinfunction "GND_Y3") (pintype "power_in"))
      (node (ref "U1") (pin "Y4") (pinfunction "GND_Y4") (pintype "power_in"))
      (node (ref "U1") (pin "Y8") (pinfunction "GND_Y8") (pintype "power_in"))
      (node (ref "U1") (pin "Y9") (pinfunction "GND_Y9") (pintype "power_in"))
      (node (ref "VR1") (pin "1") (pinfunction "AGND_1") (pintype "passive"))
      (node (ref "VR1") (pin "19") (pinfunction "PGND_19") (pintype "passive"))
      (node (ref "VR1") (pin "20") (pinfunction "PGND_20") (pintype "passive"))
      (node (ref "VR1") (pin "21") (pinfunction "PGND_21") (pintype "passive"))
      (node (ref "VR1") (pin "22") (pinfunction "PGND_22") (pintype "passive"))
      (node (ref "VR1") (pin "23") (pinfunction "PGND_23") (pintype "passive"))
      (node (ref "VR1") (pin "24") (pinfunction "PGND_24") (pintype "passive"))
      (node (ref "VR1") (pin "25") (pinfunction "PGND_25") (pintype "passive"))
      (node (ref "VR1") (pin "3") (pinfunction "VOSNS-_3") (pintype "passive"))
      (node (ref "VR1") (pin "38") (pinfunction "PGND_38") (pintype "passive"))
      (node (ref "VR1") (pin "39") (pinfunction "PGND_39") (pintype "passive"))
      (node (ref "VR1") (pin "45") (pinfunction "AGND_45") (pintype "passive"))
      (node (ref "VR1") (pin "5") (pinfunction "AGND_5") (pintype "passive"))
      (node (ref "VR2") (pin "1") (pinfunction "AGND_1") (pintype "passive"))
      (node (ref "VR2") (pin "19") (pinfunction "PGND_19") (pintype "passive"))
      (node (ref "VR2") (pin "20") (pinfunction "PGND_20") (pintype "passive"))
      (node (ref "VR2") (pin "21") (pinfunction "PGND_21") (pintype "passive"))
      (node (ref "VR2") (pin "22") (pinfunction "PGND_22") (pintype "passive"))
      (node (ref "VR2") (pin "23") (pinfunction "PGND_23") (pintype "passive"))
      (node (ref "VR2") (pin "24") (pinfunction "PGND_24") (pintype "passive"))
      (node (ref "VR2") (pin "25") (pinfunction "PGND_25") (pintype "passive"))
      (node (ref "VR2") (pin "3") (pinfunction "VOSNS-_3") (pintype "passive"))
      (node (ref "VR2") (pin "38") (pinfunction "PGND_38") (pintype "passive"))
      (node (ref "VR2") (pin "39") (pinfunction "PGND_39") (pintype "passive"))
      (node (ref "VR2") (pin "45") (pinfunction "AGND_45") (pintype "passive"))
      (node (ref "VR2") (pin "5") (pinfunction "AGND_5") (pintype "passive"))
      (node (ref "VR3") (pin "1") (pinfunction "AGND_1") (pintype "passive"))
      (node (ref "VR3") (pin "19") (pinfunction "PGND_19") (pintype "passive"))
      (node (ref "VR3") (pin "20") (pinfunction "PGND_20") (pintype "passive"))
      (node (ref "VR3") (pin "21") (pinfunction "PGND_21") (pintype "passive"))
      (node (ref "VR3") (pin "22") (pinfunction "PGND_22") (pintype "passive"))
      (node (ref "VR3") (pin "23") (pinfunction "PGND_23") (pintype "passive"))
      (node (ref "VR3") (pin "24") (pinfunction "PGND_24") (pintype "passive"))
      (node (ref "VR3") (pin "25") (pinfunction "PGND_25") (pintype "passive"))
      (node (ref "VR3") (pin "3") (pinfunction "VOSNS-_3") (pintype "passive"))
      (node (ref "VR3") (pin "38") (pinfunction "PGND_38") (pintype "passive"))
      (node (ref "VR3") (pin "39") (pinfunction "PGND_39") (pintype "passive"))
      (node (ref "VR3") (pin "45") (pinfunction "AGND_45") (pintype "passive"))
      (node (ref "VR3") (pin "5") (pinfunction "AGND_5") (pintype "passive"))
      (node (ref "VR4") (pin "1") (pinfunction "AGND_1") (pintype "passive"))
      (node (ref "VR4") (pin "19") (pinfunction "PGND_19") (pintype "passive"))
      (node (ref "VR4") (pin "20") (pinfunction "PGND_20") (pintype "passive"))
      (node (ref "VR4") (pin "21") (pinfunction "PGND_21") (pintype "passive"))
      (node (ref "VR4") (pin "22") (pinfunction "PGND_22") (pintype "passive"))
      (node (ref "VR4") (pin "23") (pinfunction "PGND_23") (pintype "passive"))
      (node (ref "VR4") (pin "24") (pinfunction "PGND_24") (pintype "passive"))
      (node (ref "VR4") (pin "25") (pinfunction "PGND_25") (pintype "passive"))
      (node (ref "VR4") (pin "3") (pinfunction "VOSNS-_3") (pintype "passive"))
      (node (ref "VR4") (pin "38") (pinfunction "PGND_38") (pintype "passive"))
      (node (ref "VR4") (pin "39") (pinfunction "PGND_39") (pintype "passive"))
      (node (ref "VR4") (pin "45") (pinfunction "AGND_45") (pintype "passive"))
      (node (ref "VR4") (pin "5") (pinfunction "AGND_5") (pintype "passive"))
      (node (ref "VR5") (pin "1") (pinfunction "AGND_1") (pintype "passive"))
      (node (ref "VR5") (pin "19") (pinfunction "PGND_19") (pintype "passive"))
      (node (ref "VR5") (pin "20") (pinfunction "PGND_20") (pintype "passive"))
      (node (ref "VR5") (pin "21") (pinfunction "PGND_21") (pintype "passive"))
      (node (ref "VR5") (pin "22") (pinfunction "PGND_22") (pintype "passive"))
      (node (ref "VR5") (pin "23") (pinfunction "PGND_23") (pintype "passive"))
      (node (ref "VR5") (pin "24") (pinfunction "PGND_24") (pintype "passive"))
      (node (ref "VR5") (pin "25") (pinfunction "PGND_25") (pintype "passive"))
      (node (ref "VR5") (pin "3") (pinfunction "VOSNS-_3") (pintype "passive"))
      (node (ref "VR5") (pin "38") (pinfunction "PGND_38") (pintype "passive"))
      (node (ref "VR5") (pin "39") (pinfunction "PGND_39") (pintype "passive"))
      (node (ref "VR5") (pin "45") (pinfunction "AGND_45") (pintype "passive"))
      (node (ref "VR5") (pin "5") (pinfunction "AGND_5") (pintype "passive"))
      (node (ref "VR6") (pin "1") (pinfunction "AGND_1") (pintype "passive"))
      (node (ref "VR6") (pin "19") (pinfunction "PGND_19") (pintype "passive"))
      (node (ref "VR6") (pin "20") (pinfunction "PGND_20") (pintype "passive"))
      (node (ref "VR6") (pin "21") (pinfunction "PGND_21") (pintype "passive"))
      (node (ref "VR6") (pin "22") (pinfunction "PGND_22") (pintype "passive"))
      (node (ref "VR6") (pin "23") (pinfunction "PGND_23") (pintype "passive"))
      (node (ref "VR6") (pin "24") (pinfunction "PGND_24") (pintype "passive"))
      (node (ref "VR6") (pin "25") (pinfunction "PGND_25") (pintype "passive"))
      (node (ref "VR6") (pin "3") (pinfunction "VOSNS-_3") (pintype "passive"))
      (node (ref "VR6") (pin "38") (pinfunction "PGND_38") (pintype "passive"))
      (node (ref "VR6") (pin "39") (pinfunction "PGND_39") (pintype "passive"))
      (node (ref "VR6") (pin "45") (pinfunction "AGND_45") (pintype "passive"))
      (node (ref "VR6") (pin "5") (pinfunction "AGND_5") (pintype "passive"))
    )
    (net (code "10") (name "Net-(C41-Pad2)") (class "Default")
      (node (ref "C41") (pin "2") (pinfunction "2_2") (pintype "passive"))
      (node (ref "R34") (pin "1") (pinfunction "1_1") (pintype "passive"))
      (node (ref "R37") (pin "1") (pinfunction "1_1") (pintype "passive"))
      (node (ref "VR1") (pin "26") (pinfunction "VCC_26") (pintype "passive"))
      (node (ref "VR1") (pin "6") (pinfunction "VCC_6") (pintype "passive"))
    )
    (net (code "11") (name "Net-(C44-Pad2)") (class "Default")
      (node (ref "C44") (pin "2") (pinfunction "2_2") (pintype "passive"))
      (node (ref "VR2") (pin "26") (pinfunction "VCC_26") (pintype "passive"))
      (node (ref "VR2") (pin "6") (pinfunction "VCC_6") (pintype "passive"))
    )
    (net (code "12") (name "Net-(C52-Pad2)") (class "Default")
      (node (ref "C52") (pin "2") (pinfunction "2_2") (pintype "passive"))
      (node (ref "R41") (pin "1") (pinfunction "1_1") (pintype "passive"))
      (node (ref "VR3") (pin "26") (pinfunction "VCC_26") (pintype "passive"))
      (node (ref "VR3") (pin "6") (pinfunction "VCC_6") (pintype "passive"))
    )
    (net (code "13") (name "Net-(C60-Pad2)") (class "Default")
      (node (ref "C60") (pin "2") (pinfunction "2_2") (pintype "passive"))
      (node (ref "R45") (pin "1") (pinfunction "1_1") (pintype "passive"))
      (node (ref "R57") (pin "1") (pinfunction "1_1") (pintype "passive"))
      (node (ref "VR4") (pin "26") (pinfunction "VCC_26") (pintype "passive"))
      (node (ref "VR4") (pin "6") (pinfunction "VCC_6") (pintype "passive"))
    )
    (net (code "14") (name "Net-(C68-Pad2)") (class "Default")
      (node (ref "C68") (pin "2") (pinfunction "2_2") (pintype "passive"))
      (node (ref "R49") (pin "1") (pinfunction "1_1") (pintype "passive"))
      (node (ref "VR5") (pin "26") (pinfunction "VCC_26") (pintype "passive"))
      (node (ref "VR5") (pin "6") (pinfunction "VCC_6") (pintype "passive"))
    )
    (net (code "15") (name "Net-(C76-Pad2)") (class "Default")
      (node (ref "C76") (pin "2") (pinfunction "2_2") (pintype "passive"))
      (node (ref "R53") (pin "1") (pinfunction "1_1") (pintype "passive"))
      (node (ref "VR6") (pin "26") (pinfunction "VCC_26") (pintype "passive"))
      (node (ref "VR6") (pin "6") (pinfunction "VCC_6") (pintype "passive"))
    )
    (net (code "16") (name "Net-(U1N-VCCADC_0)") (class "Default")
      (node (ref "FB1") (pin "1") (pinfunction "1_1") (pintype "passive"))
      (node (ref "U1") (pin "P13") (pinfunction "VCCADC_0_P13") (pintype "power_in"))
    )
    (net (code "17") (name "Net-(VR1-ADDR)") (class "Default")
      (node (ref "R38") (pin "1") (pinfunction "1_1") (pintype "passive"))
      (node (ref "VR1") (pin "43") (pinfunction "ADDR_43") (pintype "passive"))
    )
    (net (code "18") (name "Net-(VR1-CTRL)") (class "Default")
      (node (ref "R39") (pin "1") (pinfunction "1_1") (pintype "passive"))
      (node (ref "R59") (pin "1") (pinfunction "1_1") (pintype "passive"))
      (node (ref "VR1") (pin "31") (pinfunction "CTRL_31") (pintype "passive"))
      (node (ref "VR2") (pin "31") (pinfunction "CTRL_31") (pintype "passive"))
    )
    (net (code "19") (name "Net-(VR1-ISUM)") (class "Default")
      (node (ref "VR1") (pin "44") (pinfunction "ISUM_44") (pintype "passive"))
      (node (ref "VR2") (pin "44") (pinfunction "ISUM_44") (pintype "passive"))
    )
    (net (code "20") (name "Net-(VR1-PASS)") (class "Default")
      (node (ref "VR1") (pin "35") (pinfunction "PASS_35") (pintype "passive"))
      (node (ref "VR2") (pin "36") (pinfunction "TAKE_36") (pintype "passive"))
    )
    (net (code "21") (name "Net-(VR1-SET)") (class "Default")
      (node (ref "VR1") (pin "37") (pinfunction "SET_37") (pintype "passive"))
      (node (ref "VR2") (pin "37") (pinfunction "SET_37") (pintype "passive"))
    )
    (net (code "22") (name "Net-(VR1-TAKE)") (class "Default")
      (node (ref "R34") (pin "2") (pinfunction "2_2") (pintype "passive"))
      (node (ref "VR1") (pin "36") (pinfunction "TAKE_36") (pintype "passive"))
      (node (ref "VR2") (pin "35") (pinfunction "PASS_35") (pintype "passive"))
    )
    (net (code "23") (name "Net-(VR1-VOSNS+)") (class "Default")
      (node (ref "C36") (pin "2") (pinfunction "2_2") (pintype "passive"))
      (node (ref "R35") (pin "1") (pinfunction "1_1") (pintype "passive"))
      (node (ref "R36") (pin "1") (pinfunction "1_1") (pintype "passive"))
      (node (ref "VR1") (pin "4") (pinfunction "VOSNS+_4") (pintype "passive"))
      (node (ref "VR2") (pin "4") (pinfunction "VOSNS+_4") (pintype "passive"))
    )
    (net (code "24") (name "Net-(VR2-ADDR)") (class "Default")
      (node (ref "R40") (pin "1") (pinfunction "1_1") (pintype "passive"))
      (node (ref "VR2") (pin "43") (pinfunction "ADDR_43") (pintype "passive"))
    )
    (net (code "25") (name "Net-(VR3-ADDR)") (class "Default")
      (node (ref "R44") (pin "1") (pinfunction "1_1") (pintype "passive"))
      (node (ref "VR3") (pin "43") (pinfunction "ADDR_43") (pintype "passive"))
    )
    (net (code "26") (name "Net-(VR3-PASS)") (class "Default")
      (node (ref "R41") (pin "2") (pinfunction "2_2") (pintype "passive"))
      (node (ref "VR3") (pin "35") (pinfunction "PASS_35") (pintype "passive"))
      (node (ref "VR3") (pin "36") (pinfunction "TAKE_36") (pintype "passive"))
    )
    (net (code "27") (name "Net-(VR3-VOSNS+)") (class "Default")
      (node (ref "C47") (pin "2") (pinfunction "2_2") (pintype "passive"))
      (node (ref "R42") (pin "1") (pinfunction "1_1") (pintype "passive"))
      (node (ref "R43") (pin "1") (pinfunction "1_1") (pintype "passive"))
      (node (ref "VR3") (pin "4") (pinfunction "VOSNS+_4") (pintype "passive"))
    )
    (net (code "28") (name "Net-(VR4-ADDR)") (class "Default")
      (node (ref "R48") (pin "1") (pinfunction "1_1") (pintype "passive"))
      (node (ref "VR4") (pin "43") (pinfunction "ADDR_43") (pintype "passive"))
    )
    (net (code "29") (name "Net-(VR4-PASS)") (class "Default")
      (node (ref "R45") (pin "2") (pinfunction "2_2") (pintype "passive"))
      (node (ref "VR4") (pin "35") (pinfunction "PASS_35") (pintype "passive"))
      (node (ref "VR4") (pin "36") (pinfunction "TAKE_36") (pintype "passive"))
    )
    (net (code "30") (name "Net-(VR4-VOSNS+)") (class "Default")
      (node (ref "C55") (pin "2") (pinfunction "2_2") (pintype "passive"))
      (node (ref "R46") (pin "1") (pinfunction "1_1") (pintype "passive"))
      (node (ref "R47") (pin "1") (pinfunction "1_1") (pintype "passive"))
      (node (ref "VR4") (pin "4") (pinfunction "VOSNS+_4") (pintype "passive"))
    )
    (net (code "31") (name "Net-(VR5-ADDR)") (class "Default")
      (node (ref "R52") (pin "1") (pinfunction "1_1") (pintype "passive"))
      (node (ref "VR5") (pin "43") (pinfunction "ADDR_43") (pintype "passive"))
    )
    (net (code "32") (name "Net-(VR5-PASS)") (class "Default")
      (node (ref "R49") (pin "2") (pinfunction "2_2") (pintype "passive"))
      (node (ref "VR5") (pin "35") (pinfunction "PASS_35") (pintype "passive"))
      (node (ref "VR5") (pin "36") (pinfunction "TAKE_36") (pintype "passive"))
    )
    (net (code "33") (name "Net-(VR5-VOSNS+)") (class "Default")
      (node (ref "C63") (pin "2") (pinfunction "2_2") (pintype "passive"))
      (node (ref "R50") (pin "1") (pinfunction "1_1") (pintype "passive"))
      (node (ref "R51") (pin "1") (pinfunction "1_1") (pintype "passive"))
      (node (ref "VR5") (pin "4") (pinfunction "VOSNS+_4") (pintype "passive"))
    )
    (net (code "34") (name "Net-(VR6-ADDR)") (class "Default")
      (node (ref "R56") (pin "1") (pinfunction "1_1") (pintype "passive"))
      (node (ref "VR6") (pin "43") (pinfunction "ADDR_43") (pintype "passive"))
    )
    (net (code "35") (name "Net-(VR6-PASS)") (class "Default")
      (node (ref "R53") (pin "2") (pinfunction "2_2") (pintype "passive"))
      (node (ref "VR6") (pin "35") (pinfunction "PASS_35") (pintype "passive"))
      (node (ref "VR6") (pin "36") (pinfunction "TAKE_36") (pintype "passive"))
    )
    (net (code "36") (name "Net-(VR6-VOSNS+)") (class "Default")
      (node (ref "C71") (pin "2") (pinfunction "2_2") (pintype "passive"))
      (node (ref "R54") (pin "1") (pinfunction "1_1") (pintype "passive"))
      (node (ref "R55") (pin "1") (pinfunction "1_1") (pintype "passive"))
      (node (ref "VR6") (pin "4") (pinfunction "VOSNS+_4") (pintype "passive"))
    )
    (net (code "37") (name "POK_1.0V") (class "Default")
      (node (ref "R37") (pin "2") (pinfunction "2_2") (pintype "passive"))
      (node (ref "VR1") (pin "32") (pinfunction "PG_32") (pintype "passive"))
      (node (ref "VR2") (pin "32") (pinfunction "PG_32") (pintype "passive"))
      (node (ref "VR3") (pin "31") (pinfunction "CTRL_31") (pintype "passive"))
      (node (ref "VR4") (pin "31") (pinfunction "CTRL_31") (pintype "passive"))
      (node (ref "VR5") (pin "31") (pinfunction "CTRL_31") (pintype "passive"))
      (node (ref "VR6") (pin "31") (pinfunction "CTRL_31") (pintype "passive"))
    )
    (net (code "38") (name "POK_1.35V") (class "Default")
      (node (ref "R57") (pin "2") (pinfunction "2_2") (pintype "passive"))
      (node (ref "VR4") (pin "32") (pinfunction "PG_32") (pintype "passive"))
    )
    (net (code "39") (name "VIN") (class "Default")
      (node (ref "C34") (pin "2") (pinfunction "2_2") (pintype "passive"))
      (node (ref "C35") (pin "2") (pinfunction "2_2") (pintype "passive"))
      (node (ref "C42") (pin "2") (pinfunction "2_2") (pintype "passive"))
      (node (ref "C43") (pin "2") (pinfunction "2_2") (pintype "passive"))
      (node (ref "C45") (pin "2") (pinfunction "2_2") (pintype "passive"))
      (node (ref "C46") (pin "2") (pinfunction "2_2") (pintype "passive"))
      (node (ref "C53") (pin "2") (pinfunction "2_2") (pintype "passive"))
      (node (ref "C54") (pin "2") (pinfunction "2_2") (pintype "passive"))
      (node (ref "C61") (pin "2") (pinfunction "2_2") (pintype "passive"))
      (node (ref "C62") (pin "2") (pinfunction "2_2") (pintype "passive"))
      (node (ref "C69") (pin "2") (pinfunction "2_2") (pintype "passive"))
      (node (ref "C70") (pin "2") (pinfunction "2_2") (pintype "passive"))
      (node (ref "R39") (pin "2") (pinfunction "2_2") (pintype "passive"))
      (node (ref "VR1") (pin "40") (pinfunction "VIN_40") (pintype "passive"))
      (node (ref "VR1") (pin "41") (pinfunction "VIN_41") (pintype "passive"))
      (node (ref "VR2") (pin "40") (pinfunction "VIN_40") (pintype "passive"))
      (node (ref "VR2") (pin "41") (pinfunction "VIN_41") (pintype "passive"))
      (node (ref "VR3") (pin "40") (pinfunction "VIN_40") (pintype "passive"))
      (node (ref "VR3") (pin "41") (pinfunction "VIN_41") (pintype "passive"))
      (node (ref "VR4") (pin "40") (pinfunction "VIN_40") (pintype "passive"))
      (node (ref "VR4") (pin "41") (pinfunction "VIN_41") (pintype "passive"))
      (node (ref "VR5") (pin "40") (pinfunction "VIN_40") (pintype "passive"))
      (node (ref "VR5") (pin "41") (pinfunction "VIN_41") (pintype "passive"))
      (node (ref "VR6") (pin "40") (pinfunction "VIN_40") (pintype "passive"))
      (node (ref "VR6") (pin "41") (pinfunction "VIN_41") (pintype "passive"))
    )
    (net (code "40") (name "unconnected-(U1N-VCCBATT_0-PadG13)") (class "Default")
      (node (ref "U1") (pin "G13") (pinfunction "VCCBATT_0_G13") (pintype "power_in"))
    )
    (net (code "41") (name "unconnected-(VR1-BST-Pad7)") (class "Default")
      (node (ref "VR1") (pin "7") (pinfunction "BST_7") (pintype "passive"))
    )
    (net (code "42") (name "unconnected-(VR1-IREF-Pad2)") (class "Default")
      (node (ref "VR1") (pin "2") (pinfunction "IREF_2") (pintype "passive"))
    )
    (net (code "43") (name "unconnected-(VR1-N{slash}C-Pad16)") (class "Default")
      (node (ref "VR1") (pin "16") (pinfunction "N/C_16") (pintype "passive"))
    )
    (net (code "44") (name "unconnected-(VR1-N{slash}C-Pad17)") (class "Default")
      (node (ref "VR1") (pin "17") (pinfunction "N/C_17") (pintype "passive"))
    )
    (net (code "45") (name "unconnected-(VR1-N{slash}C-Pad18)") (class "Default")
      (node (ref "VR1") (pin "18") (pinfunction "N/C_18") (pintype "passive"))
    )
    (net (code "46") (name "unconnected-(VR1-N{slash}C-Pad33)") (class "Default")
      (node (ref "VR1") (pin "33") (pinfunction "N/C_33") (pintype "passive"))
    )
    (net (code "47") (name "unconnected-(VR1-N{slash}C-Pad34)") (class "Default")
      (node (ref "VR1") (pin "34") (pinfunction "N/C_34") (pintype "passive"))
    )
    (net (code "48") (name "unconnected-(VR1-N{slash}C-Pad42)") (class "Default")
      (node (ref "VR1") (pin "42") (pinfunction "N/C_42") (pintype "passive"))
    )
    (net (code "49") (name "unconnected-(VR1-TP-Pad8)") (class "Default")
      (node (ref "VR1") (pin "8") (pinfunction "TP_8") (pintype "passive"))
    )
    (net (code "50") (name "unconnected-(VR1-VDRV-Pad27)") (class "Default")
      (node (ref "VR1") (pin "27") (pinfunction "VDRV_27") (pintype "passive"))
    )
    (net (code "51") (name "unconnected-(VR2-BST-Pad7)") (class "Default")
      (node (ref "VR2") (pin "7") (pinfunction "BST_7") (pintype "passive"))
    )
    (net (code "52") (name "unconnected-(VR2-IREF-Pad2)") (class "Default")
      (node (ref "VR2") (pin "2") (pinfunction "IREF_2") (pintype "passive"))
    )
    (net (code "53") (name "unconnected-(VR2-N{slash}C-Pad16)") (class "Default")
      (node (ref "VR2") (pin "16") (pinfunction "N/C_16") (pintype "passive"))
    )
    (net (code "54") (name "unconnected-(VR2-N{slash}C-Pad17)") (class "Default")
      (node (ref "VR2") (pin "17") (pinfunction "N/C_17") (pintype "passive"))
    )
    (net (code "55") (name "unconnected-(VR2-N{slash}C-Pad18)") (class "Default")
      (node (ref "VR2") (pin "18") (pinfunction "N/C_18") (pintype "passive"))
    )
    (net (code "56") (name "unconnected-(VR2-N{slash}C-Pad33)") (class "Default")
      (node (ref "VR2") (pin "33") (pinfunction "N/C_33") (pintype "passive"))
    )
    (net (code "57") (name "unconnected-(VR2-N{slash}C-Pad34)") (class "Default")
      (node (ref "VR2") (pin "34") (pinfunction "N/C_34") (pintype "passive"))
    )
    (net (code "58") (name "unconnected-(VR2-N{slash}C-Pad42)") (class "Default")
      (node (ref "VR2") (pin "42") (pinfunction "N/C_42") (pintype "passive"))
    )
    (net (code "59") (name "unconnected-(VR2-TP-Pad8)") (class "Default")
      (node (ref "VR2") (pin "8") (pinfunction "TP_8") (pintype "passive"))
    )
    (net (code "60") (name "unconnected-(VR2-VDRV-Pad27)") (class "Default")
      (node (ref "VR2") (pin "27") (pinfunction "VDRV_27") (pintype "passive"))
    )
    (net (code "61") (name "unconnected-(VR3-BST-Pad7)") (class "Default")
      (node (ref "VR3") (pin "7") (pinfunction "BST_7") (pintype "passive"))
    )
    (net (code "62") (name "unconnected-(VR3-IREF-Pad2)") (class "Default")
      (node (ref "VR3") (pin "2") (pinfunction "IREF_2") (pintype "passive"))
    )
    (net (code "63") (name "unconnected-(VR3-ISUM-Pad44)") (class "Default")
      (node (ref "VR3") (pin "44") (pinfunction "ISUM_44") (pintype "passive"))
    )
    (net (code "64") (name "unconnected-(VR3-N{slash}C-Pad16)") (class "Default")
      (node (ref "VR3") (pin "16") (pinfunction "N/C_16") (pintype "passive"))
    )
    (net (code "65") (name "unconnected-(VR3-N{slash}C-Pad17)") (class "Default")
      (node (ref "VR3") (pin "17") (pinfunction "N/C_17") (pintype "passive"))
    )
    (net (code "66") (name "unconnected-(VR3-N{slash}C-Pad18)") (class "Default")
      (node (ref "VR3") (pin "18") (pinfunction "N/C_18") (pintype "passive"))
    )
    (net (code "67") (name "unconnected-(VR3-N{slash}C-Pad33)") (class "Default")
      (node (ref "VR3") (pin "33") (pinfunction "N/C_33") (pintype "passive"))
    )
    (net (code "68") (name "unconnected-(VR3-N{slash}C-Pad34)") (class "Default")
      (node (ref "VR3") (pin "34") (pinfunction "N/C_34") (pintype "passive"))
    )
    (net (code "69") (name "unconnected-(VR3-N{slash}C-Pad42)") (class "Default")
      (node (ref "VR3") (pin "42") (pinfunction "N/C_42") (pintype "passive"))
    )
    (net (code "70") (name "unconnected-(VR3-PG-Pad32)") (class "Default")
      (node (ref "VR3") (pin "32") (pinfunction "PG_32") (pintype "passive"))
    )
    (net (code "71") (name "unconnected-(VR3-SET-Pad37)") (class "Default")
      (node (ref "VR3") (pin "37") (pinfunction "SET_37") (pintype "passive"))
    )
    (net (code "72") (name "unconnected-(VR3-TP-Pad8)") (class "Default")
      (node (ref "VR3") (pin "8") (pinfunction "TP_8") (pintype "passive"))
    )
    (net (code "73") (name "unconnected-(VR3-VDRV-Pad27)") (class "Default")
      (node (ref "VR3") (pin "27") (pinfunction "VDRV_27") (pintype "passive"))
    )
    (net (code "74") (name "unconnected-(VR4-BST-Pad7)") (class "Default")
      (node (ref "VR4") (pin "7") (pinfunction "BST_7") (pintype "passive"))
    )
    (net (code "75") (name "unconnected-(VR4-IREF-Pad2)") (class "Default")
      (node (ref "VR4") (pin "2") (pinfunction "IREF_2") (pintype "passive"))
    )
    (net (code "76") (name "unconnected-(VR4-ISUM-Pad44)") (class "Default")
      (node (ref "VR4") (pin "44") (pinfunction "ISUM_44") (pintype "passive"))
    )
    (net (code "77") (name "unconnected-(VR4-N{slash}C-Pad16)") (class "Default")
      (node (ref "VR4") (pin "16") (pinfunction "N/C_16") (pintype "passive"))
    )
    (net (code "78") (name "unconnected-(VR4-N{slash}C-Pad17)") (class "Default")
      (node (ref "VR4") (pin "17") (pinfunction "N/C_17") (pintype "passive"))
    )
    (net (code "79") (name "unconnected-(VR4-N{slash}C-Pad18)") (class "Default")
      (node (ref "VR4") (pin "18") (pinfunction "N/C_18") (pintype "passive"))
    )
    (net (code "80") (name "unconnected-(VR4-N{slash}C-Pad33)") (class "Default")
      (node (ref "VR4") (pin "33") (pinfunction "N/C_33") (pintype "passive"))
    )
    (net (code "81") (name "unconnected-(VR4-N{slash}C-Pad34)") (class "Default")
      (node (ref "VR4") (pin "34") (pinfunction "N/C_34") (pintype "passive"))
    )
    (net (code "82") (name "unconnected-(VR4-N{slash}C-Pad42)") (class "Default")
      (node (ref "VR4") (pin "42") (pinfunction "N/C_42") (pintype "passive"))
    )
    (net (code "83") (name "unconnected-(VR4-SET-Pad37)") (class "Default")
      (node (ref "VR4") (pin "37") (pinfunction "SET_37") (pintype "passive"))
    )
    (net (code "84") (name "unconnected-(VR4-TP-Pad8)") (class "Default")
      (node (ref "VR4") (pin "8") (pinfunction "TP_8") (pintype "passive"))
    )
    (net (code "85") (name "unconnected-(VR4-VDRV-Pad27)") (class "Default")
      (node (ref "VR4") (pin "27") (pinfunction "VDRV_27") (pintype "passive"))
    )
    (net (code "86") (name "unconnected-(VR5-BST-Pad7)") (class "Default")
      (node (ref "VR5") (pin "7") (pinfunction "BST_7") (pintype "passive"))
    )
    (net (code "87") (name "unconnected-(VR5-IREF-Pad2)") (class "Default")
      (node (ref "VR5") (pin "2") (pinfunction "IREF_2") (pintype "passive"))
    )
    (net (code "88") (name "unconnected-(VR5-ISUM-Pad44)") (class "Default")
      (node (ref "VR5") (pin "44") (pinfunction "ISUM_44") (pintype "passive"))
    )
    (net (code "89") (name "unconnected-(VR5-N{slash}C-Pad16)") (class "Default")
      (node (ref "VR5") (pin "16") (pinfunction "N/C_16") (pintype "passive"))
    )
    (net (code "90") (name "unconnected-(VR5-N{slash}C-Pad17)") (class "Default")
      (node (ref "VR5") (pin "17") (pinfunction "N/C_17") (pintype "passive"))
    )
    (net (code "91") (name "unconnected-(VR5-N{slash}C-Pad18)") (class "Default")
      (node (ref "VR5") (pin "18") (pinfunction "N/C_18") (pintype "passive"))
    )
    (net (code "92") (name "unconnected-(VR5-N{slash}C-Pad33)") (class "Default")
      (node (ref "VR5") (pin "33") (pinfunction "N/C_33") (pintype "passive"))
    )
    (net (code "93") (name "unconnected-(VR5-N{slash}C-Pad34)") (class "Default")
      (node (ref "VR5") (pin "34") (pinfunction "N/C_34") (pintype "passive"))
    )
    (net (code "94") (name "unconnected-(VR5-N{slash}C-Pad42)") (class "Default")
      (node (ref "VR5") (pin "42") (pinfunction "N/C_42") (pintype "passive"))
    )
    (net (code "95") (name "unconnected-(VR5-PG-Pad32)") (class "Default")
      (node (ref "VR5") (pin "32") (pinfunction "PG_32") (pintype "passive"))
    )
    (net (code "96") (name "unconnected-(VR5-SET-Pad37)") (class "Default")
      (node (ref "VR5") (pin "37") (pinfunction "SET_37") (pintype "passive"))
    )
    (net (code "97") (name "unconnected-(VR5-TP-Pad8)") (class "Default")
      (node (ref "VR5") (pin "8") (pinfunction "TP_8") (pintype "passive"))
    )
    (net (code "98") (name "unconnected-(VR5-VDRV-Pad27)") (class "Default")
      (node (ref "VR5") (pin "27") (pinfunction "VDRV_27") (pintype "passive"))
    )
    (net (code "99") (name "unconnected-(VR6-BST-Pad7)") (class "Default")
      (node (ref "VR6") (pin "7") (pinfunction "BST_7") (pintype "passive"))
    )
    (net (code "100") (name "unconnected-(VR6-IREF-Pad2)") (class "Default")
      (node (ref "VR6") (pin "2") (pinfunction "IREF_2") (pintype "passive"))
    )
    (net (code "101") (name "unconnected-(VR6-ISUM-Pad44)") (class "Default")
      (node (ref "VR6") (pin "44") (pinfunction "ISUM_44") (pintype "passive"))
    )
    (net (code "102") (name "unconnected-(VR6-N{slash}C-Pad16)") (class "Default")
      (node (ref "VR6") (pin "16") (pinfunction "N/C_16") (pintype "passive"))
    )
    (net (code "103") (name "unconnected-(VR6-N{slash}C-Pad17)") (class "Default")
      (node (ref "VR6") (pin "17") (pinfunction "N/C_17") (pintype "passive"))
    )
    (net (code "104") (name "unconnected-(VR6-N{slash}C-Pad18)") (class "Default")
      (node (ref "VR6") (pin "18") (pinfunction "N/C_18") (pintype "passive"))
    )
    (net (code "105") (name "unconnected-(VR6-N{slash}C-Pad33)") (class "Default")
      (node (ref "VR6") (pin "33") (pinfunction "N/C_33") (pintype "passive"))
    )
    (net (code "106") (name "unconnected-(VR6-N{slash}C-Pad34)") (class "Default")
      (node (ref "VR6") (pin "34") (pinfunction "N/C_34") (pintype "passive"))
    )
    (net (code "107") (name "unconnected-(VR6-N{slash}C-Pad42)") (class "Default")
      (node (ref "VR6") (pin "42") (pinfunction "N/C_42") (pintype "passive"))
    )
    (net (code "108") (name "unconnected-(VR6-PG-Pad32)") (class "Default")
      (node (ref "VR6") (pin "32") (pinfunction "PG_32") (pintype "passive"))
    )
    (net (code "109") (name "unconnected-(VR6-SET-Pad37)") (class "Default")
      (node (ref "VR6") (pin "37") (pinfunction "SET_37") (pintype "passive"))
    )
    (net (code "110") (name "unconnected-(VR6-TP-Pad8)") (class "Default")
      (node (ref "VR6") (pin "8") (pinfunction "TP_8") (pintype "passive"))
    )
    (net (code "111") (name "unconnected-(VR6-VDRV-Pad27)") (class "Default")
      (node (ref "VR6") (pin "27") (pinfunction "VDRV_27") (pintype "passive"))
    )
  )
)
